# VOID01_REVA.net
KiCad netlist of a schematic drawn in EAGLE
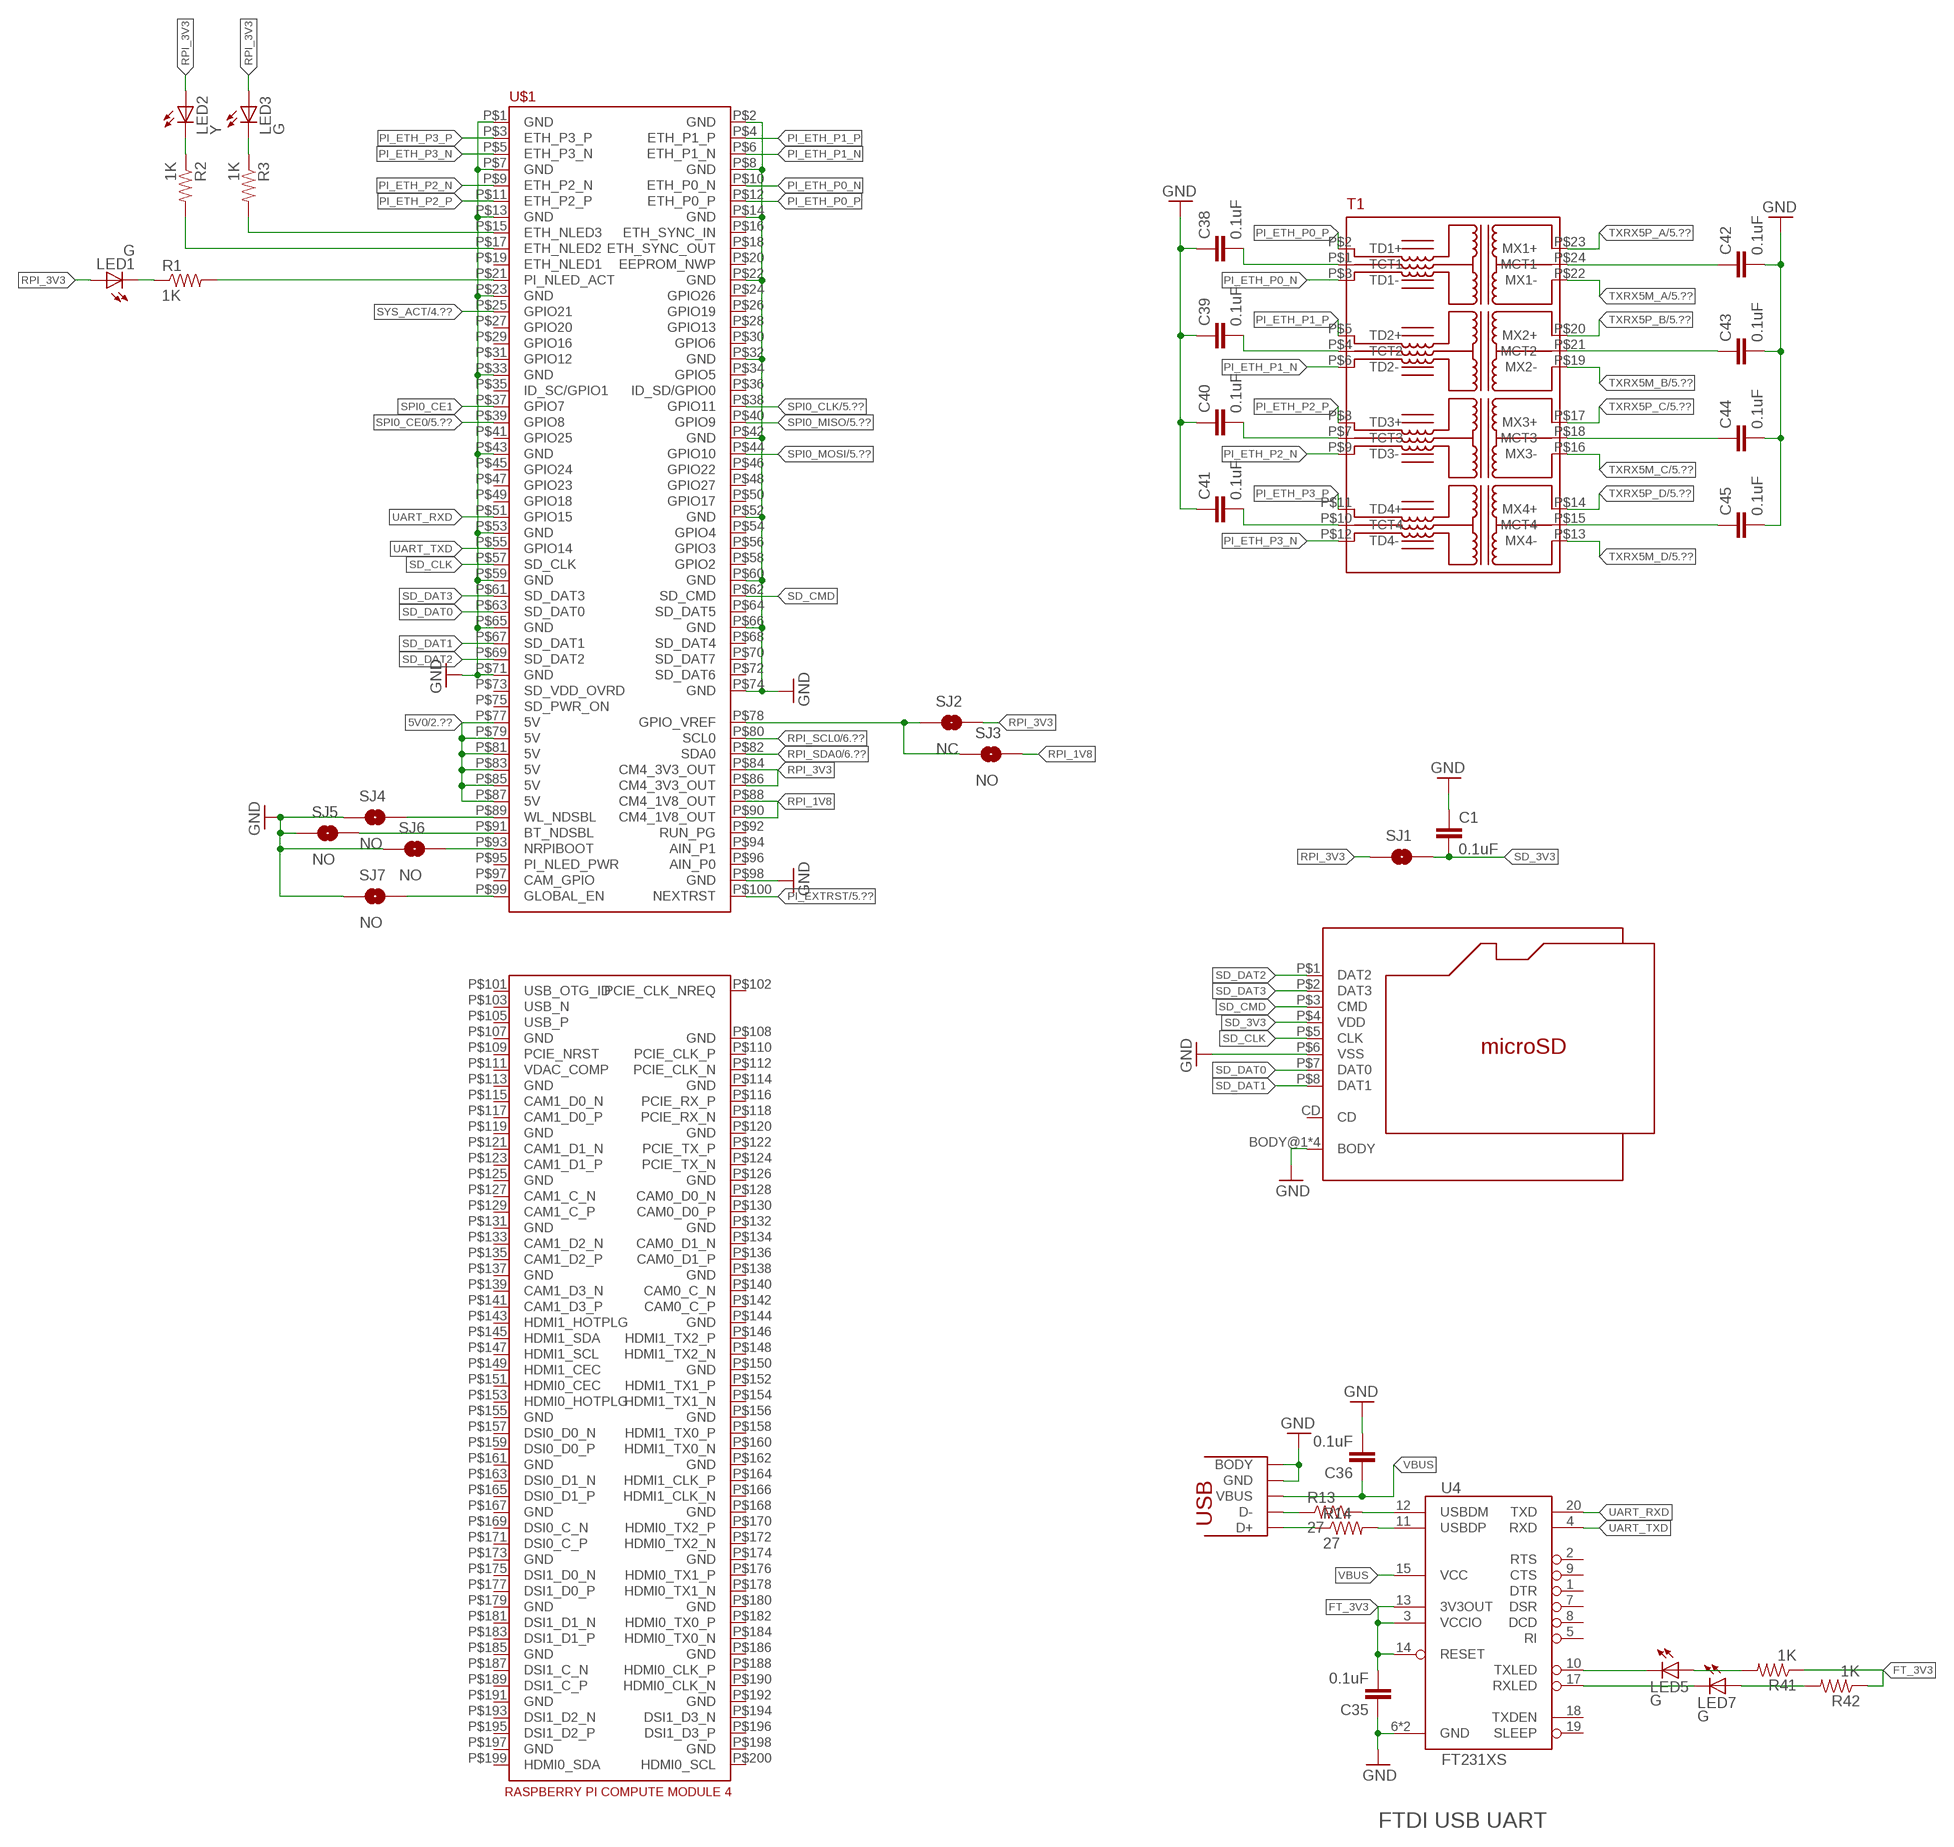
[diagram p0: schematic, sheet 1]
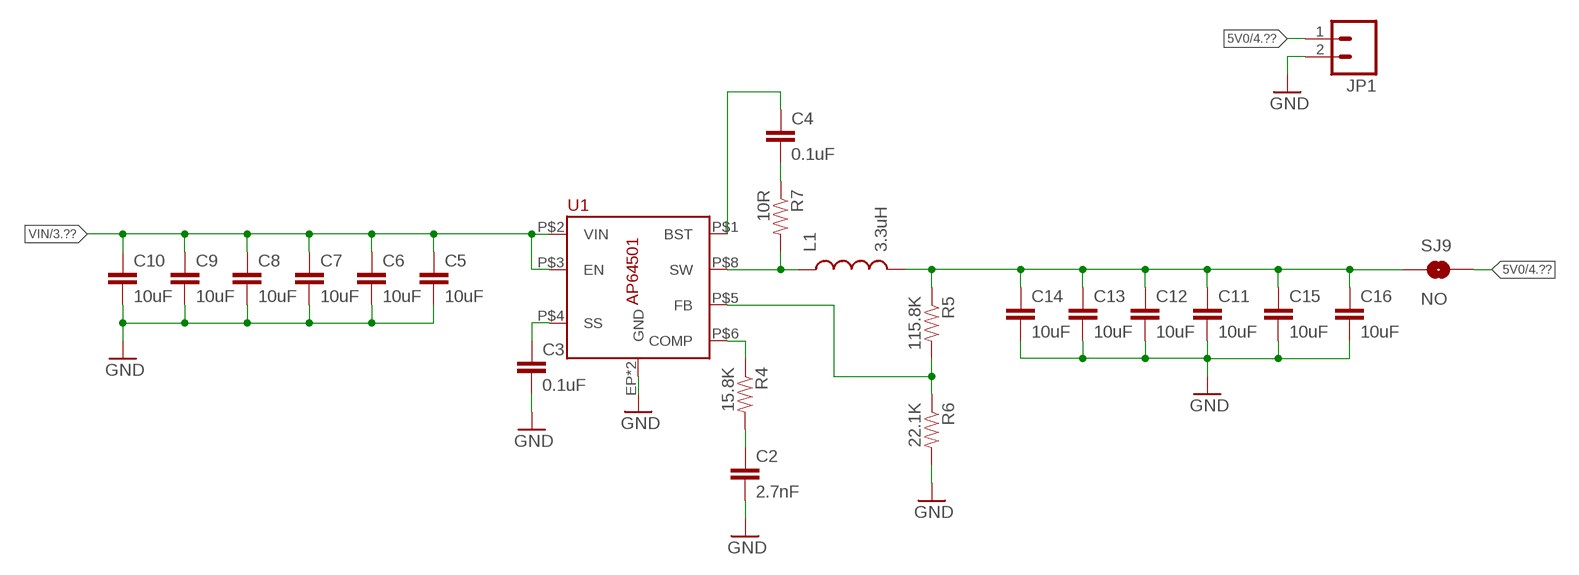
[diagram p1: schematic, sheet 2]
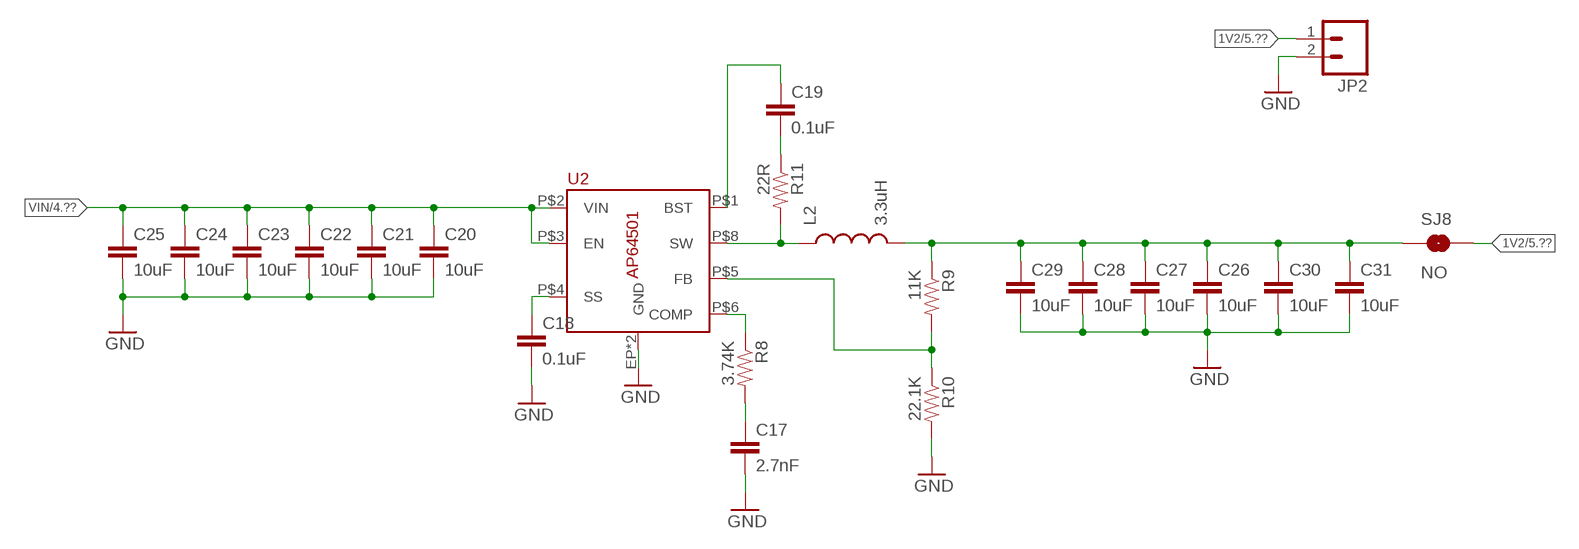
[diagram p2: schematic, sheet 3]
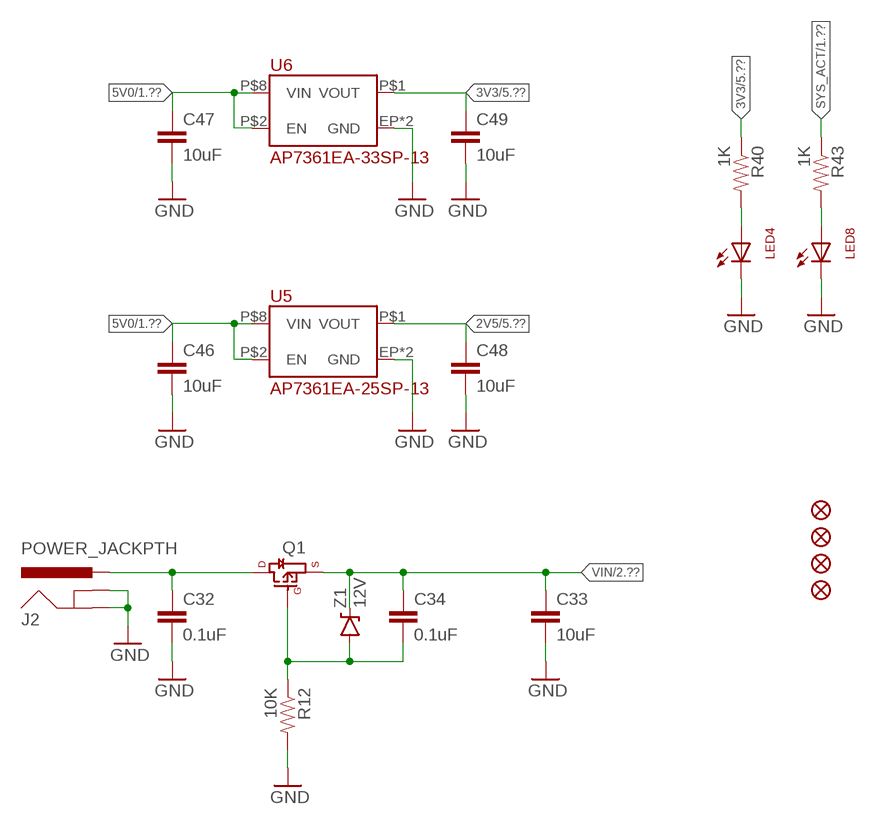
[diagram p3: schematic, sheet 4]
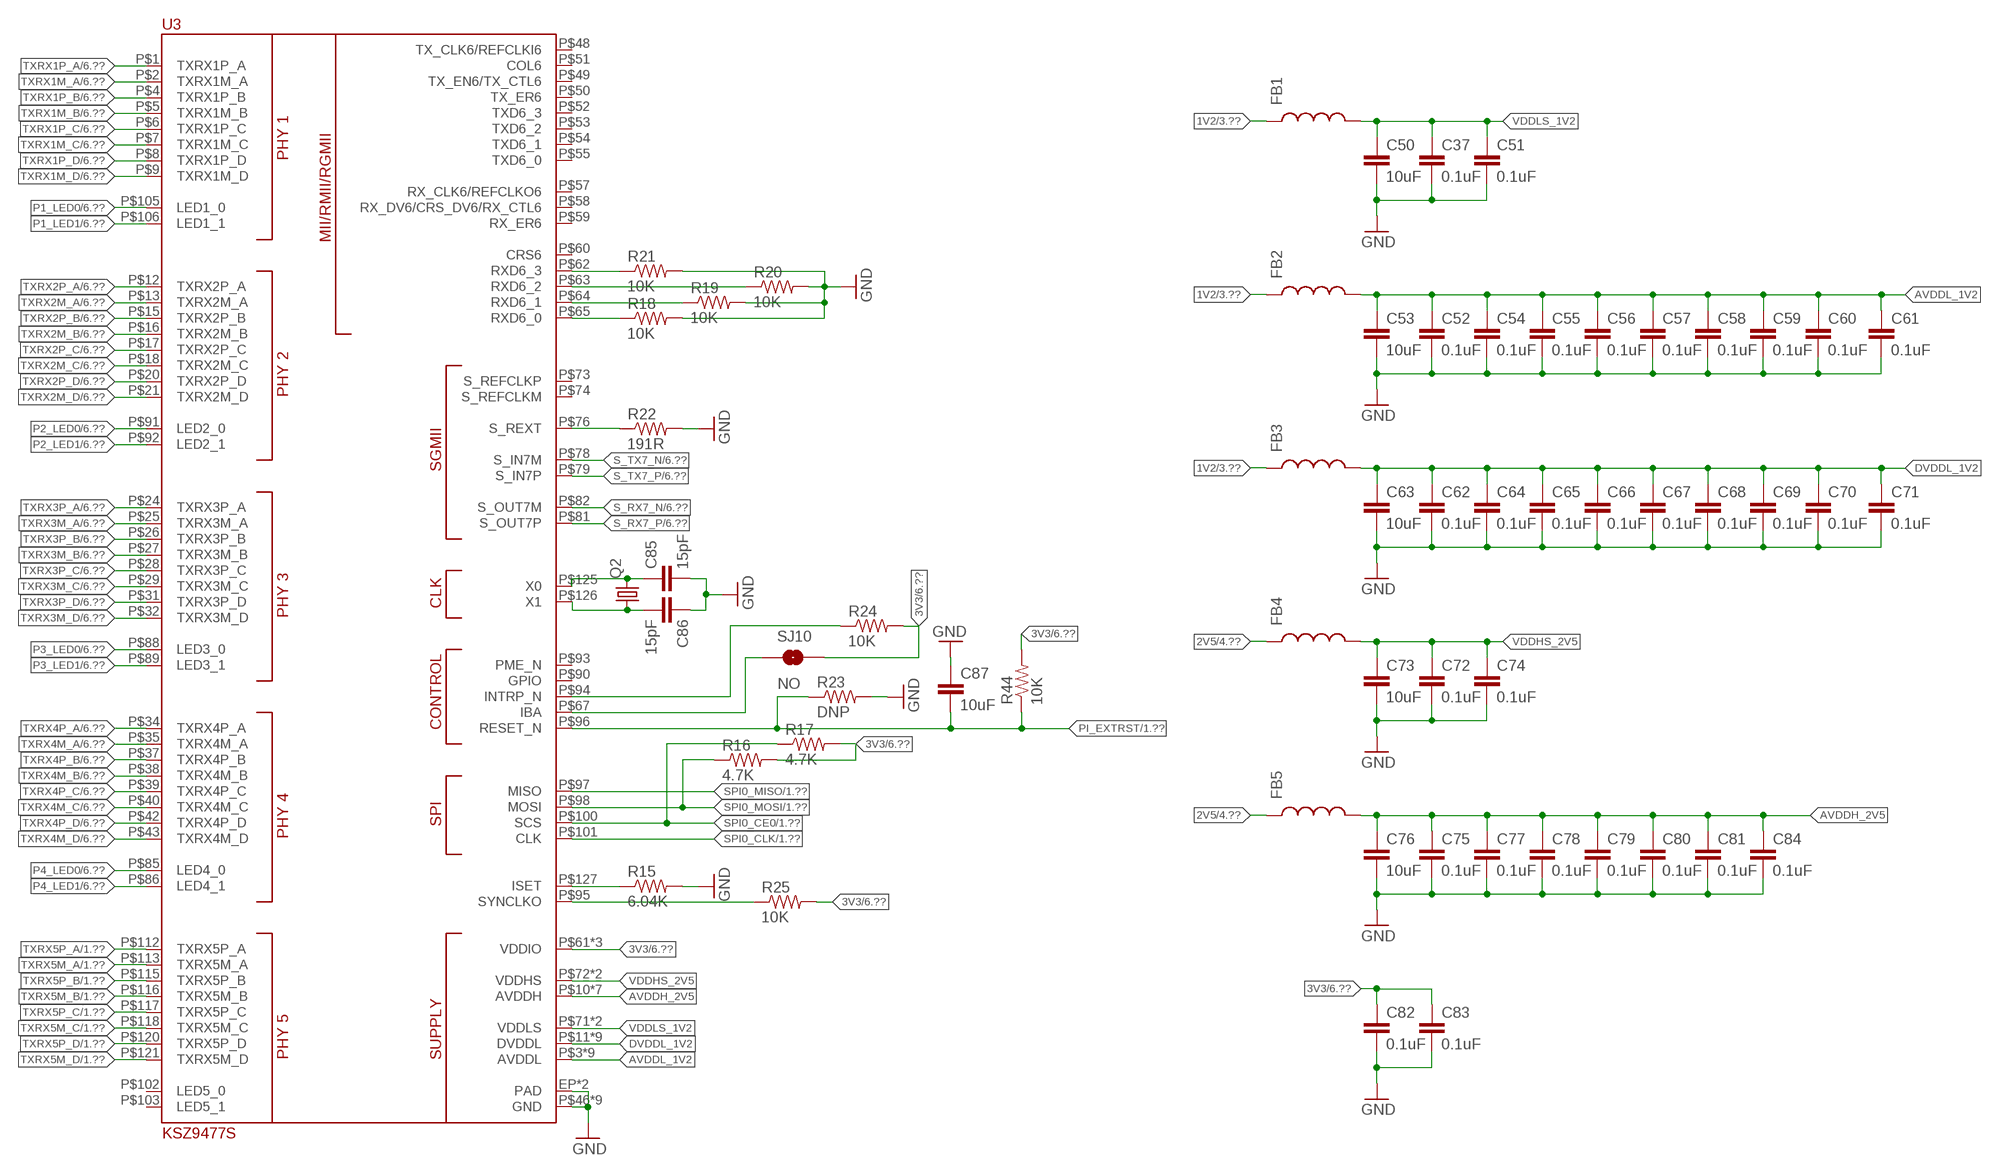
[diagram p4: schematic, sheet 5]
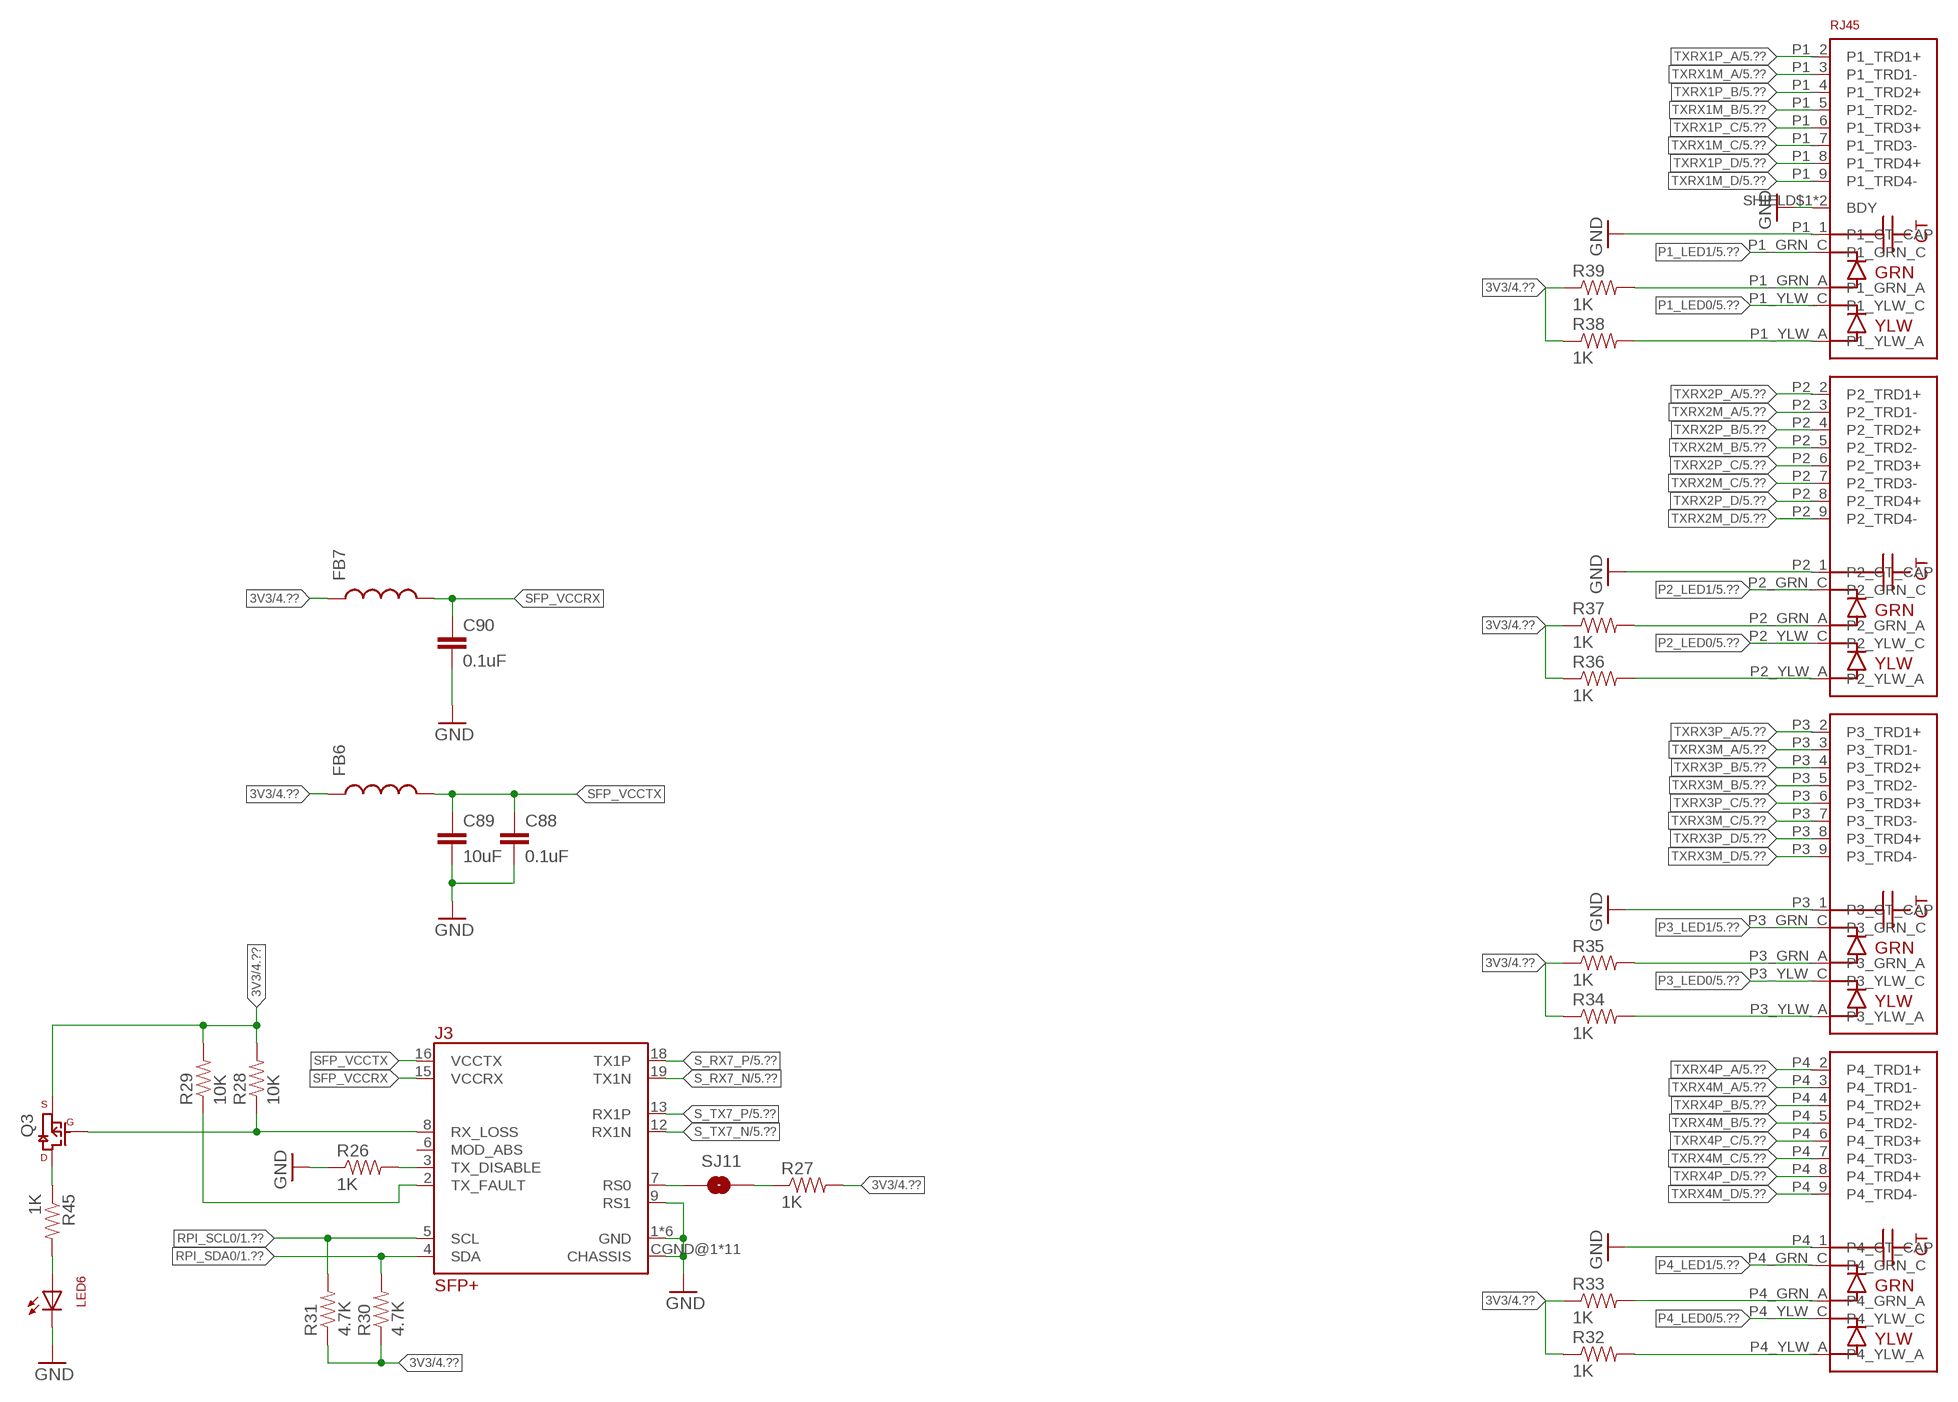
[diagram p5: schematic, sheet 6]

(export (version "E")
  (design (tool "Eeschema 10.0.6"))
  (components
    (comp (ref "C1")
      (value "0.1uF")
      (footprint "eagle-import:0603-CAP")
      (libsource (lib "eagle-import") (part "CAP0603-CAP"))
    )
    (comp (ref "C35")
      (value "0.1uF")
      (footprint "eagle-import:0603-CAP")
      (libsource (lib "eagle-import") (part "CAP0603-CAP"))
    )
    (comp (ref "C36")
      (value "0.1uF")
      (footprint "eagle-import:0603-CAP")
      (libsource (lib "eagle-import") (part "CAP0603-CAP"))
    )
    (comp (ref "C38")
      (value "0.1uF")
      (footprint "eagle-import:0603-CAP")
      (libsource (lib "eagle-import") (part "CAP0603-CAP"))
    )
    (comp (ref "C39")
      (value "0.1uF")
      (footprint "eagle-import:0603-CAP")
      (libsource (lib "eagle-import") (part "CAP0603-CAP"))
    )
    (comp (ref "C40")
      (value "0.1uF")
      (footprint "eagle-import:0603-CAP")
      (libsource (lib "eagle-import") (part "CAP0603-CAP"))
    )
    (comp (ref "C41")
      (value "0.1uF")
      (footprint "eagle-import:0603-CAP")
      (libsource (lib "eagle-import") (part "CAP0603-CAP"))
    )
    (comp (ref "C42")
      (value "0.1uF")
      (footprint "eagle-import:0603-CAP")
      (libsource (lib "eagle-import") (part "CAP0603-CAP"))
    )
    (comp (ref "C43")
      (value "0.1uF")
      (footprint "eagle-import:0603-CAP")
      (libsource (lib "eagle-import") (part "CAP0603-CAP"))
    )
    (comp (ref "C44")
      (value "0.1uF")
      (footprint "eagle-import:0603-CAP")
      (libsource (lib "eagle-import") (part "CAP0603-CAP"))
    )
    (comp (ref "C45")
      (value "0.1uF")
      (footprint "eagle-import:0603-CAP")
      (libsource (lib "eagle-import") (part "CAP0603-CAP"))
    )
    (comp (ref "J1")
      (value "MICROSD")
      (footprint "eagle-import:MSD-4-A")
      (libsource (lib "eagle-import") (part "MICROSD"))
    )
    (comp (ref "LED1")
      (value "G")
      (footprint "eagle-import:LED-0603")
      (libsource (lib "eagle-import") (part "LED0603"))
    )
    (comp (ref "LED2")
      (value "Y")
      (footprint "eagle-import:LED-0603")
      (libsource (lib "eagle-import") (part "LED0603"))
    )
    (comp (ref "LED3")
      (value "G")
      (footprint "eagle-import:LED-0603")
      (libsource (lib "eagle-import") (part "LED0603"))
    )
    (comp (ref "LED5")
      (value "G")
      (footprint "eagle-import:LED-0603")
      (libsource (lib "eagle-import") (part "LED0603"))
    )
    (comp (ref "LED7")
      (value "G")
      (footprint "eagle-import:LED-0603")
      (libsource (lib "eagle-import") (part "LED0603"))
    )
    (comp (ref "R1")
      (value "1K")
      (footprint "eagle-import:0402-RES")
      (libsource (lib "eagle-import") (part "RESISTOR0402-RES"))
    )
    (comp (ref "R2")
      (value "1K")
      (footprint "eagle-import:0402-RES")
      (libsource (lib "eagle-import") (part "RESISTOR0402-RES"))
    )
    (comp (ref "R3")
      (value "1K")
      (footprint "eagle-import:0402-RES")
      (libsource (lib "eagle-import") (part "RESISTOR0402-RES"))
    )
    (comp (ref "R13")
      (value "27")
      (footprint "eagle-import:0603-RES")
      (libsource (lib "eagle-import") (part "RESISTOR0603-RES"))
    )
    (comp (ref "R14")
      (value "27")
      (footprint "eagle-import:0603-RES")
      (libsource (lib "eagle-import") (part "RESISTOR0603-RES"))
    )
    (comp (ref "R41")
      (value "1K")
      (footprint "eagle-import:0603-RES")
      (libsource (lib "eagle-import") (part "RESISTOR0603-RES"))
    )
    (comp (ref "R42")
      (value "1K")
      (footprint "eagle-import:0603-RES")
      (libsource (lib "eagle-import") (part "RESISTOR0603-RES"))
    )
    (comp (ref "SJ1")
      (value "SOLDERJUMPERTRACE")
      (footprint "eagle-import:SJ_2S-TRACE")
      (libsource (lib "eagle-import") (part "SOLDERJUMPERTRACE"))
    )
    (comp (ref "SJ2")
      (value "NC")
      (footprint "eagle-import:SJ_2S-TRACE")
      (libsource (lib "eagle-import") (part "SOLDERJUMPERTRACE"))
    )
    (comp (ref "SJ3")
      (value "NO")
      (footprint "eagle-import:SJ_2S-NO")
      (libsource (lib "eagle-import") (part "SOLDERJUMPERNO"))
    )
    (comp (ref "SJ4")
      (value "NO")
      (footprint "eagle-import:SJ_2S-NO")
      (libsource (lib "eagle-import") (part "SOLDERJUMPERNO"))
    )
    (comp (ref "SJ5")
      (value "NO")
      (footprint "eagle-import:SJ_2S-NO")
      (libsource (lib "eagle-import") (part "SOLDERJUMPERNO"))
    )
    (comp (ref "SJ6")
      (value "NO")
      (footprint "eagle-import:SJ_2S-NO")
      (libsource (lib "eagle-import") (part "SOLDERJUMPERNO"))
    )
    (comp (ref "SJ7")
      (value "NO")
      (footprint "eagle-import:SJ_2S-NO")
      (libsource (lib "eagle-import") (part "SOLDERJUMPERNO"))
    )
    (comp (ref "T1")
      (value "HX6098NL")
      (footprint "eagle-import:HX6098NL")
      (libsource (lib "eagle-import") (part "HX6098NL"))
    )
    (comp (ref "U$1")
      (value "RPI-CM4")
      (footprint "eagle-import:RPI-CM4")
      (libsource (lib "eagle-import") (part "RPI-CM4"))
    )
    (comp (ref "U$2")
      (value "USB-MICROB")
      (footprint "eagle-import:USB-MICROB-10118192")
      (libsource (lib "eagle-import") (part "USB-MICROB"))
    )
    (comp (ref "U4")
      (value "FT231XS")
      (footprint "eagle-import:SSOP-20")
      (libsource (lib "eagle-import") (part "FT231XS"))
    )
    (comp (ref "C37")
      (value "0.1uF")
      (footprint "eagle-import:0402-CAP")
      (libsource (lib "eagle-import") (part "CAP0402-CAP"))
    )
    (comp (ref "C50")
      (value "10uF")
      (footprint "eagle-import:1206")
      (libsource (lib "eagle-import") (part "CAP1206"))
    )
    (comp (ref "C51")
      (value "0.1uF")
      (footprint "eagle-import:0402-CAP")
      (libsource (lib "eagle-import") (part "CAP0402-CAP"))
    )
    (comp (ref "C52")
      (value "0.1uF")
      (footprint "eagle-import:0402-CAP")
      (libsource (lib "eagle-import") (part "CAP0402-CAP"))
    )
    (comp (ref "C53")
      (value "10uF")
      (footprint "eagle-import:1206")
      (libsource (lib "eagle-import") (part "CAP1206"))
    )
    (comp (ref "C54")
      (value "0.1uF")
      (footprint "eagle-import:0402-CAP")
      (libsource (lib "eagle-import") (part "CAP0402-CAP"))
    )
    (comp (ref "C55")
      (value "0.1uF")
      (footprint "eagle-import:0402-CAP")
      (libsource (lib "eagle-import") (part "CAP0402-CAP"))
    )
    (comp (ref "C56")
      (value "0.1uF")
      (footprint "eagle-import:0402-CAP")
      (libsource (lib "eagle-import") (part "CAP0402-CAP"))
    )
    (comp (ref "C57")
      (value "0.1uF")
      (footprint "eagle-import:0402-CAP")
      (libsource (lib "eagle-import") (part "CAP0402-CAP"))
    )
    (comp (ref "C58")
      (value "0.1uF")
      (footprint "eagle-import:0402-CAP")
      (libsource (lib "eagle-import") (part "CAP0402-CAP"))
    )
    (comp (ref "C59")
      (value "0.1uF")
      (footprint "eagle-import:0402-CAP")
      (libsource (lib "eagle-import") (part "CAP0402-CAP"))
    )
    (comp (ref "C60")
      (value "0.1uF")
      (footprint "eagle-import:0402-CAP")
      (libsource (lib "eagle-import") (part "CAP0402-CAP"))
    )
    (comp (ref "C61")
      (value "0.1uF")
      (footprint "eagle-import:0402-CAP")
      (libsource (lib "eagle-import") (part "CAP0402-CAP"))
    )
    (comp (ref "C62")
      (value "0.1uF")
      (footprint "eagle-import:0402-CAP")
      (libsource (lib "eagle-import") (part "CAP0402-CAP"))
    )
    (comp (ref "C63")
      (value "10uF")
      (footprint "eagle-import:1206")
      (libsource (lib "eagle-import") (part "CAP1206"))
    )
    (comp (ref "C64")
      (value "0.1uF")
      (footprint "eagle-import:0402-CAP")
      (libsource (lib "eagle-import") (part "CAP0402-CAP"))
    )
    (comp (ref "C65")
      (value "0.1uF")
      (footprint "eagle-import:0402-CAP")
      (libsource (lib "eagle-import") (part "CAP0402-CAP"))
    )
    (comp (ref "C66")
      (value "0.1uF")
      (footprint "eagle-import:0402-CAP")
      (libsource (lib "eagle-import") (part "CAP0402-CAP"))
    )
    (comp (ref "C67")
      (value "0.1uF")
      (footprint "eagle-import:0402-CAP")
      (libsource (lib "eagle-import") (part "CAP0402-CAP"))
    )
    (comp (ref "C68")
      (value "0.1uF")
      (footprint "eagle-import:0402-CAP")
      (libsource (lib "eagle-import") (part "CAP0402-CAP"))
    )
    (comp (ref "C69")
      (value "0.1uF")
      (footprint "eagle-import:0402-CAP")
      (libsource (lib "eagle-import") (part "CAP0402-CAP"))
    )
    (comp (ref "C70")
      (value "0.1uF")
      (footprint "eagle-import:0402-CAP")
      (libsource (lib "eagle-import") (part "CAP0402-CAP"))
    )
    (comp (ref "C71")
      (value "0.1uF")
      (footprint "eagle-import:0402-CAP")
      (libsource (lib "eagle-import") (part "CAP0402-CAP"))
    )
    (comp (ref "C72")
      (value "0.1uF")
      (footprint "eagle-import:0402-CAP")
      (libsource (lib "eagle-import") (part "CAP0402-CAP"))
    )
    (comp (ref "C73")
      (value "10uF")
      (footprint "eagle-import:1206")
      (libsource (lib "eagle-import") (part "CAP1206"))
    )
    (comp (ref "C74")
      (value "0.1uF")
      (footprint "eagle-import:0402-CAP")
      (libsource (lib "eagle-import") (part "CAP0402-CAP"))
    )
    (comp (ref "C75")
      (value "0.1uF")
      (footprint "eagle-import:0402-CAP")
      (libsource (lib "eagle-import") (part "CAP0402-CAP"))
    )
    (comp (ref "C76")
      (value "10uF")
      (footprint "eagle-import:1206")
      (libsource (lib "eagle-import") (part "CAP1206"))
    )
    (comp (ref "C77")
      (value "0.1uF")
      (footprint "eagle-import:0402-CAP")
      (libsource (lib "eagle-import") (part "CAP0402-CAP"))
    )
    (comp (ref "C78")
      (value "0.1uF")
      (footprint "eagle-import:0402-CAP")
      (libsource (lib "eagle-import") (part "CAP0402-CAP"))
    )
    (comp (ref "C79")
      (value "0.1uF")
      (footprint "eagle-import:0402-CAP")
      (libsource (lib "eagle-import") (part "CAP0402-CAP"))
    )
    (comp (ref "C80")
      (value "0.1uF")
      (footprint "eagle-import:0402-CAP")
      (libsource (lib "eagle-import") (part "CAP0402-CAP"))
    )
    (comp (ref "C81")
      (value "0.1uF")
      (footprint "eagle-import:0402-CAP")
      (libsource (lib "eagle-import") (part "CAP0402-CAP"))
    )
    (comp (ref "C82")
      (value "0.1uF")
      (footprint "eagle-import:0402-CAP")
      (libsource (lib "eagle-import") (part "CAP0402-CAP"))
    )
    (comp (ref "C83")
      (value "0.1uF")
      (footprint "eagle-import:0402-CAP")
      (libsource (lib "eagle-import") (part "CAP0402-CAP"))
    )
    (comp (ref "C84")
      (value "0.1uF")
      (footprint "eagle-import:0402-CAP")
      (libsource (lib "eagle-import") (part "CAP0402-CAP"))
    )
    (comp (ref "C85")
      (value "15pF")
      (footprint "eagle-import:0402-CAP")
      (libsource (lib "eagle-import") (part "CAP0402-CAP"))
    )
    (comp (ref "C86")
      (value "15pF")
      (footprint "eagle-import:0402-CAP")
      (libsource (lib "eagle-import") (part "CAP0402-CAP"))
    )
    (comp (ref "C87")
      (value "10uF")
      (footprint "eagle-import:1206")
      (libsource (lib "eagle-import") (part "CAP1206"))
    )
    (comp (ref "FB1")
      (value "INDUCTOR0805")
      (footprint "eagle-import:0805")
      (libsource (lib "eagle-import") (part "INDUCTOR0805"))
    )
    (comp (ref "FB2")
      (value "INDUCTOR0805")
      (footprint "eagle-import:0805")
      (libsource (lib "eagle-import") (part "INDUCTOR0805"))
    )
    (comp (ref "FB3")
      (value "INDUCTOR0805")
      (footprint "eagle-import:0805")
      (libsource (lib "eagle-import") (part "INDUCTOR0805"))
    )
    (comp (ref "FB4")
      (value "INDUCTOR0805")
      (footprint "eagle-import:0805")
      (libsource (lib "eagle-import") (part "INDUCTOR0805"))
    )
    (comp (ref "FB5")
      (value "INDUCTOR0805")
      (footprint "eagle-import:0805")
      (libsource (lib "eagle-import") (part "INDUCTOR0805"))
    )
    (comp (ref "Q2")
      (value "CRYSTAL3.2X2.5")
      (footprint "eagle-import:CRYSTAL_3.2X2.5")
      (libsource (lib "eagle-import") (part "CRYSTAL3.2X2.5"))
    )
    (comp (ref "R15")
      (value "6.04K")
      (footprint "eagle-import:0402-RES")
      (libsource (lib "eagle-import") (part "RESISTOR0402-RES"))
    )
    (comp (ref "R16")
      (value "4.7K")
      (footprint "eagle-import:0402-RES")
      (libsource (lib "eagle-import") (part "RESISTOR0402-RES"))
    )
    (comp (ref "R17")
      (value "4.7K")
      (footprint "eagle-import:0402-RES")
      (libsource (lib "eagle-import") (part "RESISTOR0402-RES"))
    )
    (comp (ref "R18")
      (value "10K")
      (footprint "eagle-import:0402-RES")
      (libsource (lib "eagle-import") (part "RESISTOR0402-RES"))
    )
    (comp (ref "R19")
      (value "10K")
      (footprint "eagle-import:0402-RES")
      (libsource (lib "eagle-import") (part "RESISTOR0402-RES"))
    )
    (comp (ref "R20")
      (value "10K")
      (footprint "eagle-import:0402-RES")
      (libsource (lib "eagle-import") (part "RESISTOR0402-RES"))
    )
    (comp (ref "R21")
      (value "10K")
      (footprint "eagle-import:0402-RES")
      (libsource (lib "eagle-import") (part "RESISTOR0402-RES"))
    )
    (comp (ref "R22")
      (value "191R")
      (footprint "eagle-import:0402-RES")
      (libsource (lib "eagle-import") (part "RESISTOR0402-RES"))
    )
    (comp (ref "R23")
      (value "DNP")
      (footprint "eagle-import:0402-RES")
      (libsource (lib "eagle-import") (part "RESISTOR0402-RES"))
    )
    (comp (ref "R24")
      (value "10K")
      (footprint "eagle-import:0402-RES")
      (libsource (lib "eagle-import") (part "RESISTOR0402-RES"))
    )
    (comp (ref "R25")
      (value "10K")
      (footprint "eagle-import:0402-RES")
      (libsource (lib "eagle-import") (part "RESISTOR0402-RES"))
    )
    (comp (ref "R44")
      (value "10K")
      (footprint "eagle-import:0402-RES")
      (libsource (lib "eagle-import") (part "RESISTOR0402-RES"))
    )
    (comp (ref "SJ10")
      (value "NO")
      (footprint "eagle-import:SJ_2S-NO")
      (libsource (lib "eagle-import") (part "SOLDERJUMPERNO"))
    )
    (comp (ref "U3")
      (value "KSZ9477S")
      (footprint "eagle-import:TQFP-128-EP")
      (libsource (lib "eagle-import") (part "KSZ9477S"))
    )
    (comp (ref "C88")
      (value "0.1uF")
      (footprint "eagle-import:0402-CAP")
      (libsource (lib "eagle-import") (part "CAP0402-CAP"))
    )
    (comp (ref "C89")
      (value "10uF")
      (footprint "eagle-import:1206")
      (libsource (lib "eagle-import") (part "CAP1206"))
    )
    (comp (ref "C90")
      (value "0.1uF")
      (footprint "eagle-import:0402-CAP")
      (libsource (lib "eagle-import") (part "CAP0402-CAP"))
    )
    (comp (ref "FB6")
      (value "INDUCTOR0805")
      (footprint "eagle-import:0805")
      (libsource (lib "eagle-import") (part "INDUCTOR0805"))
    )
    (comp (ref "FB7")
      (value "INDUCTOR0805")
      (footprint "eagle-import:0805")
      (libsource (lib "eagle-import") (part "INDUCTOR0805"))
    )
    (comp (ref "J3")
      (value "SFP")
      (footprint "eagle-import:SFP_SOCKET_CAGE")
      (libsource (lib "eagle-import") (part "SFP+"))
    )
    (comp (ref "J4")
      (value "JXD0-4015NL")
      (footprint "eagle-import:JXD0-4015NL")
      (libsource (lib "eagle-import") (part "JXD0-4015NL"))
    )
    (comp (ref "LED6")
      (value "LED")
      (footprint "eagle-import:LED_QBL7XX80D-MP4A")
      (libsource (lib "eagle-import") (part "LED"))
    )
    (comp (ref "Q3")
      (value "MOSFET_P_CHANNELAO3423")
      (footprint "eagle-import:SOT-23")
      (libsource (lib "eagle-import") (part "MOSFET_P_CHANNELAO3423"))
    )
    (comp (ref "R26")
      (value "1K")
      (footprint "eagle-import:0402-RES")
      (libsource (lib "eagle-import") (part "RESISTOR0402-RES"))
    )
    (comp (ref "R27")
      (value "1K")
      (footprint "eagle-import:0402-RES")
      (libsource (lib "eagle-import") (part "RESISTOR0402-RES"))
    )
    (comp (ref "R28")
      (value "10K")
      (footprint "eagle-import:0603-RES")
      (libsource (lib "eagle-import") (part "RESISTOR0603-RES"))
    )
    (comp (ref "R29")
      (value "10K")
      (footprint "eagle-import:0402-RES")
      (libsource (lib "eagle-import") (part "RESISTOR0402-RES"))
    )
    (comp (ref "R30")
      (value "4.7K")
      (footprint "eagle-import:0402-RES")
      (libsource (lib "eagle-import") (part "RESISTOR0402-RES"))
    )
    (comp (ref "R31")
      (value "4.7K")
      (footprint "eagle-import:0402-RES")
      (libsource (lib "eagle-import") (part "RESISTOR0402-RES"))
    )
    (comp (ref "R32")
      (value "1K")
      (footprint "eagle-import:0603-RES")
      (libsource (lib "eagle-import") (part "RESISTOR0603-RES"))
    )
    (comp (ref "R33")
      (value "1K")
      (footprint "eagle-import:0603-RES")
      (libsource (lib "eagle-import") (part "RESISTOR0603-RES"))
    )
    (comp (ref "R34")
      (value "1K")
      (footprint "eagle-import:0603-RES")
      (libsource (lib "eagle-import") (part "RESISTOR0603-RES"))
    )
    (comp (ref "R35")
      (value "1K")
      (footprint "eagle-import:0603-RES")
      (libsource (lib "eagle-import") (part "RESISTOR0603-RES"))
    )
    (comp (ref "R36")
      (value "1K")
      (footprint "eagle-import:0603-RES")
      (libsource (lib "eagle-import") (part "RESISTOR0603-RES"))
    )
    (comp (ref "R37")
      (value "1K")
      (footprint "eagle-import:0603-RES")
      (libsource (lib "eagle-import") (part "RESISTOR0603-RES"))
    )
    (comp (ref "R38")
      (value "1K")
      (footprint "eagle-import:0603-RES")
      (libsource (lib "eagle-import") (part "RESISTOR0603-RES"))
    )
    (comp (ref "R39")
      (value "1K")
      (footprint "eagle-import:0603-RES")
      (libsource (lib "eagle-import") (part "RESISTOR0603-RES"))
    )
    (comp (ref "R45")
      (value "1K")
      (footprint "eagle-import:0603-RES")
      (libsource (lib "eagle-import") (part "RESISTOR0603-RES"))
    )
    (comp (ref "SJ11")
      (value "SOLDERJUMPERNO")
      (footprint "eagle-import:SJ_2S-NO")
      (libsource (lib "eagle-import") (part "SOLDERJUMPERNO"))
    )
    (comp (ref "C17")
      (value "2.7nF")
      (footprint "eagle-import:0603-CAP")
      (libsource (lib "eagle-import") (part "CAP0603-CAP"))
    )
    (comp (ref "C18")
      (value "0.1uF")
      (footprint "eagle-import:0603-CAP")
      (libsource (lib "eagle-import") (part "CAP0603-CAP"))
    )
    (comp (ref "C19")
      (value "0.1uF")
      (footprint "eagle-import:0603-CAP")
      (libsource (lib "eagle-import") (part "CAP0603-CAP"))
    )
    (comp (ref "C20")
      (value "10uF")
      (footprint "eagle-import:1206")
      (libsource (lib "eagle-import") (part "CAP1206"))
    )
    (comp (ref "C21")
      (value "10uF")
      (footprint "eagle-import:1206")
      (libsource (lib "eagle-import") (part "CAP1206"))
    )
    (comp (ref "C22")
      (value "10uF")
      (footprint "eagle-import:1206")
      (libsource (lib "eagle-import") (part "CAP1206"))
    )
    (comp (ref "C23")
      (value "10uF")
      (footprint "eagle-import:1206")
      (libsource (lib "eagle-import") (part "CAP1206"))
    )
    (comp (ref "C24")
      (value "10uF")
      (footprint "eagle-import:1206")
      (libsource (lib "eagle-import") (part "CAP1206"))
    )
    (comp (ref "C25")
      (value "10uF")
      (footprint "eagle-import:1206")
      (libsource (lib "eagle-import") (part "CAP1206"))
    )
    (comp (ref "C26")
      (value "10uF")
      (footprint "eagle-import:1206")
      (libsource (lib "eagle-import") (part "CAP1206"))
    )
    (comp (ref "C27")
      (value "10uF")
      (footprint "eagle-import:1206")
      (libsource (lib "eagle-import") (part "CAP1206"))
    )
    (comp (ref "C28")
      (value "10uF")
      (footprint "eagle-import:1206")
      (libsource (lib "eagle-import") (part "CAP1206"))
    )
    (comp (ref "C29")
      (value "10uF")
      (footprint "eagle-import:1206")
      (libsource (lib "eagle-import") (part "CAP1206"))
    )
    (comp (ref "C30")
      (value "10uF")
      (footprint "eagle-import:1206")
      (libsource (lib "eagle-import") (part "CAP1206"))
    )
    (comp (ref "C31")
      (value "10uF")
      (footprint "eagle-import:1206")
      (libsource (lib "eagle-import") (part "CAP1206"))
    )
    (comp (ref "JP2")
      (value "M02PTH3")
      (footprint "eagle-import:1X02_LONGPADS")
      (libsource (lib "eagle-import") (part "M02PTH3"))
    )
    (comp (ref "L2")
      (value "3.3uH")
      (footprint "eagle-import:SRN6045TA")
      (libsource (lib "eagle-import") (part "INDUCTORSRN6045TA"))
    )
    (comp (ref "R8")
      (value "3.74K")
      (footprint "eagle-import:0603-RES")
      (libsource (lib "eagle-import") (part "RESISTOR0603-RES"))
    )
    (comp (ref "R9")
      (value "11K")
      (footprint "eagle-import:0603-RES")
      (libsource (lib "eagle-import") (part "RESISTOR0603-RES"))
    )
    (comp (ref "R10")
      (value "22.1K")
      (footprint "eagle-import:0603-RES")
      (libsource (lib "eagle-import") (part "RESISTOR0603-RES"))
    )
    (comp (ref "R11")
      (value "22R")
      (footprint "eagle-import:0603-RES")
      (libsource (lib "eagle-import") (part "RESISTOR0603-RES"))
    )
    (comp (ref "SJ8")
      (value "NO")
      (footprint "eagle-import:SJ_2S-NO")
      (libsource (lib "eagle-import") (part "SOLDERJUMPERNO"))
    )
    (comp (ref "U2")
      (value "AP64501")
      (footprint "eagle-import:SO-8EP")
      (libsource (lib "eagle-import") (part "AP64501"))
    )
    (comp (ref "C2")
      (value "2.7nF")
      (footprint "eagle-import:0603-CAP")
      (libsource (lib "eagle-import") (part "CAP0603-CAP"))
    )
    (comp (ref "C3")
      (value "0.1uF")
      (footprint "eagle-import:0603-CAP")
      (libsource (lib "eagle-import") (part "CAP0603-CAP"))
    )
    (comp (ref "C4")
      (value "0.1uF")
      (footprint "eagle-import:0603-CAP")
      (libsource (lib "eagle-import") (part "CAP0603-CAP"))
    )
    (comp (ref "C5")
      (value "10uF")
      (footprint "eagle-import:1206")
      (libsource (lib "eagle-import") (part "CAP1206"))
    )
    (comp (ref "C6")
      (value "10uF")
      (footprint "eagle-import:1206")
      (libsource (lib "eagle-import") (part "CAP1206"))
    )
    (comp (ref "C7")
      (value "10uF")
      (footprint "eagle-import:1206")
      (libsource (lib "eagle-import") (part "CAP1206"))
    )
    (comp (ref "C8")
      (value "10uF")
      (footprint "eagle-import:1206")
      (libsource (lib "eagle-import") (part "CAP1206"))
    )
    (comp (ref "C9")
      (value "10uF")
      (footprint "eagle-import:1206")
      (libsource (lib "eagle-import") (part "CAP1206"))
    )
    (comp (ref "C10")
      (value "10uF")
      (footprint "eagle-import:1206")
      (libsource (lib "eagle-import") (part "CAP1206"))
    )
    (comp (ref "C11")
      (value "10uF")
      (footprint "eagle-import:1206")
      (libsource (lib "eagle-import") (part "CAP1206"))
    )
    (comp (ref "C12")
      (value "10uF")
      (footprint "eagle-import:1206")
      (libsource (lib "eagle-import") (part "CAP1206"))
    )
    (comp (ref "C13")
      (value "10uF")
      (footprint "eagle-import:1206")
      (libsource (lib "eagle-import") (part "CAP1206"))
    )
    (comp (ref "C14")
      (value "10uF")
      (footprint "eagle-import:1206")
      (libsource (lib "eagle-import") (part "CAP1206"))
    )
    (comp (ref "C15")
      (value "10uF")
      (footprint "eagle-import:1206")
      (libsource (lib "eagle-import") (part "CAP1206"))
    )
    (comp (ref "C16")
      (value "10uF")
      (footprint "eagle-import:1206")
      (libsource (lib "eagle-import") (part "CAP1206"))
    )
    (comp (ref "JP1")
      (value "M02PTH3")
      (footprint "eagle-import:1X02_LONGPADS")
      (libsource (lib "eagle-import") (part "M02PTH3"))
    )
    (comp (ref "L1")
      (value "3.3uH")
      (footprint "eagle-import:SRN6045TA")
      (libsource (lib "eagle-import") (part "INDUCTORSRN6045TA"))
    )
    (comp (ref "R4")
      (value "15.8K")
      (footprint "eagle-import:0603-RES")
      (libsource (lib "eagle-import") (part "RESISTOR0603-RES"))
    )
    (comp (ref "R5")
      (value "115.8K")
      (footprint "eagle-import:0603-RES")
      (libsource (lib "eagle-import") (part "RESISTOR0603-RES"))
    )
    (comp (ref "R6")
      (value "22.1K")
      (footprint "eagle-import:0603-RES")
      (libsource (lib "eagle-import") (part "RESISTOR0603-RES"))
    )
    (comp (ref "R7")
      (value "10R")
      (footprint "eagle-import:0603-RES")
      (libsource (lib "eagle-import") (part "RESISTOR0603-RES"))
    )
    (comp (ref "SJ9")
      (value "NO")
      (footprint "eagle-import:SJ_2S-NO")
      (libsource (lib "eagle-import") (part "SOLDERJUMPERNO"))
    )
    (comp (ref "U1")
      (value "AP64501")
      (footprint "eagle-import:SO-8EP")
      (libsource (lib "eagle-import") (part "AP64501"))
    )
    (comp (ref "C32")
      (value "0.1uF")
      (footprint "eagle-import:0603-CAP")
      (libsource (lib "eagle-import") (part "CAP0603-CAP"))
    )
    (comp (ref "C33")
      (value "10uF")
      (footprint "eagle-import:1206")
      (libsource (lib "eagle-import") (part "CAP1206"))
    )
    (comp (ref "C34")
      (value "0.1uF")
      (footprint "eagle-import:0603-CAP")
      (libsource (lib "eagle-import") (part "CAP0603-CAP"))
    )
    (comp (ref "C46")
      (value "10uF")
      (footprint "eagle-import:1206")
      (libsource (lib "eagle-import") (part "CAP1206"))
    )
    (comp (ref "C47")
      (value "10uF")
      (footprint "eagle-import:1206")
      (libsource (lib "eagle-import") (part "CAP1206"))
    )
    (comp (ref "C48")
      (value "10uF")
      (footprint "eagle-import:1206")
      (libsource (lib "eagle-import") (part "CAP1206"))
    )
    (comp (ref "C49")
      (value "10uF")
      (footprint "eagle-import:1206")
      (libsource (lib "eagle-import") (part "CAP1206"))
    )
    (comp (ref "FID1")
      (value "FIDUCIAL")
      (footprint "eagle-import:FIDUCIAL")
      (libsource (lib "eagle-import") (part "FIDUCIAL"))
    )
    (comp (ref "FID2")
      (value "FIDUCIAL")
      (footprint "eagle-import:FIDUCIAL")
      (libsource (lib "eagle-import") (part "FIDUCIAL"))
    )
    (comp (ref "FID3")
      (value "FIDUCIAL")
      (footprint "eagle-import:FIDUCIAL")
      (libsource (lib "eagle-import") (part "FIDUCIAL"))
    )
    (comp (ref "FID4")
      (value "FIDUCIAL")
      (footprint "eagle-import:FIDUCIAL")
      (libsource (lib "eagle-import") (part "FIDUCIAL"))
    )
    (comp (ref "J2")
      (value "POWER_JACKPTH")
      (footprint "eagle-import:POWER_JACK_PTH")
      (libsource (lib "eagle-import") (part "POWER_JACKPTH"))
    )
    (comp (ref "LED4")
      (value "LED")
      (footprint "eagle-import:LED_QBL7XX80D-MP4A")
      (libsource (lib "eagle-import") (part "LED"))
    )
    (comp (ref "LED8")
      (value "LED")
      (footprint "eagle-import:LED_QBL7XX80D-MP4A")
      (libsource (lib "eagle-import") (part "LED"))
    )
    (comp (ref "Q1")
      (value "MOSFET_P_CHANNELDMP4015SSS")
      (footprint "eagle-import:SO08")
      (libsource (lib "eagle-import") (part "MOSFET_P_CHANNELDMP4015SSS"))
    )
    (comp (ref "R12")
      (value "10K")
      (footprint "eagle-import:0603-RES")
      (libsource (lib "eagle-import") (part "RESISTOR0603-RES"))
    )
    (comp (ref "R40")
      (value "1K")
      (footprint "eagle-import:0603-RES")
      (libsource (lib "eagle-import") (part "RESISTOR0603-RES"))
    )
    (comp (ref "R43")
      (value "1K")
      (footprint "eagle-import:0603-RES")
      (libsource (lib "eagle-import") (part "RESISTOR0603-RES"))
    )
    (comp (ref "U5")
      (value "AP7361EA-25SP-13")
      (footprint "eagle-import:SO-8EP")
      (libsource (lib "eagle-import") (part "AP7361EA_SO8_EP"))
    )
    (comp (ref "U6")
      (value "AP7361EA-33SP-13")
      (footprint "eagle-import:SO-8EP")
      (libsource (lib "eagle-import") (part "AP7361EA_SO8_EP"))
    )
    (comp (ref "Z1")
      (value "12V")
      (footprint "eagle-import:SOT-23")
      (libsource (lib "eagle-import") (part "DIODE-ZENERSOT-23"))
    )
  )
  (nets
    (net (code "1") (name "1V2") (class "Default")
      (node (ref "FB1") (pin "1") (pinfunction "1_1") (pintype "passive"))
      (node (ref "FB2") (pin "1") (pinfunction "1_1") (pintype "passive"))
      (node (ref "FB3") (pin "1") (pinfunction "1_1") (pintype "passive"))
      (node (ref "JP2") (pin "1") (pinfunction "1_1") (pintype "passive"))
      (node (ref "SJ8") (pin "2") (pinfunction "2_2") (pintype "passive"))
    )
    (net (code "2") (name "2V5") (class "Default")
      (node (ref "C48") (pin "1") (pinfunction "1_1") (pintype "passive"))
      (node (ref "FB4") (pin "1") (pinfunction "1_1") (pintype "passive"))
      (node (ref "FB5") (pin "1") (pinfunction "1_1") (pintype "passive"))
      (node (ref "U5") (pin "P$1") (pinfunction "VOUT_P$1") (pintype "bidirectional"))
    )
    (net (code "3") (name "3V3") (class "Default")
      (node (ref "C49") (pin "1") (pinfunction "1_1") (pintype "passive"))
      (node (ref "C82") (pin "1") (pinfunction "1_1") (pintype "passive"))
      (node (ref "C83") (pin "1") (pinfunction "1_1") (pintype "passive"))
      (node (ref "FB6") (pin "1") (pinfunction "1_1") (pintype "passive"))
      (node (ref "FB7") (pin "1") (pinfunction "1_1") (pintype "passive"))
      (node (ref "Q3") (pin "2") (pinfunction "S_2") (pintype "bidirectional"))
      (node (ref "R16") (pin "2") (pinfunction "2_2") (pintype "passive"))
      (node (ref "R17") (pin "2") (pinfunction "2_2") (pintype "passive"))
      (node (ref "R24") (pin "2") (pinfunction "2_2") (pintype "passive"))
      (node (ref "R25") (pin "2") (pinfunction "2_2") (pintype "passive"))
      (node (ref "R27") (pin "2") (pinfunction "2_2") (pintype "passive"))
      (node (ref "R28") (pin "2") (pinfunction "2_2") (pintype "passive"))
      (node (ref "R29") (pin "2") (pinfunction "2_2") (pintype "passive"))
      (node (ref "R30") (pin "1") (pinfunction "1_1") (pintype "passive"))
      (node (ref "R31") (pin "1") (pinfunction "1_1") (pintype "passive"))
      (node (ref "R32") (pin "1") (pinfunction "1_1") (pintype "passive"))
      (node (ref "R33") (pin "1") (pinfunction "1_1") (pintype "passive"))
      (node (ref "R34") (pin "1") (pinfunction "1_1") (pintype "passive"))
      (node (ref "R35") (pin "1") (pinfunction "1_1") (pintype "passive"))
      (node (ref "R36") (pin "1") (pinfunction "1_1") (pintype "passive"))
      (node (ref "R37") (pin "1") (pinfunction "1_1") (pintype "passive"))
      (node (ref "R38") (pin "1") (pinfunction "1_1") (pintype "passive"))
      (node (ref "R39") (pin "1") (pinfunction "1_1") (pintype "passive"))
      (node (ref "R40") (pin "1") (pinfunction "1_1") (pintype "passive"))
      (node (ref "R44") (pin "2") (pinfunction "2_2") (pintype "passive"))
      (node (ref "SJ10") (pin "2") (pinfunction "2_2") (pintype "passive"))
      (node (ref "U3") (pin "P$61") (pinfunction "VDDIO_P$61") (pintype "bidirectional"))
      (node (ref "U3") (pin "P$68") (pinfunction "VDDIO_P$68") (pintype "bidirectional"))
      (node (ref "U3") (pin "P$99") (pinfunction "VDDIO_P$99") (pintype "bidirectional"))
      (node (ref "U6") (pin "P$1") (pinfunction "VOUT_P$1") (pintype "bidirectional"))
    )
    (net (code "4") (name "5V0") (class "Default")
      (node (ref "C46") (pin "1") (pinfunction "1_1") (pintype "passive"))
      (node (ref "C47") (pin "1") (pinfunction "1_1") (pintype "passive"))
      (node (ref "JP1") (pin "1") (pinfunction "1_1") (pintype "passive"))
      (node (ref "SJ9") (pin "2") (pinfunction "2_2") (pintype "passive"))
      (node (ref "U$1") (pin "P$77") (pinfunction "5V_P$77") (pintype "bidirectional"))
      (node (ref "U$1") (pin "P$79") (pinfunction "5V_P$79") (pintype "bidirectional"))
      (node (ref "U$1") (pin "P$81") (pinfunction "5V_P$81") (pintype "bidirectional"))
      (node (ref "U$1") (pin "P$83") (pinfunction "5V_P$83") (pintype "bidirectional"))
      (node (ref "U$1") (pin "P$85") (pinfunction "5V_P$85") (pintype "bidirectional"))
      (node (ref "U$1") (pin "P$87") (pinfunction "5V_P$87") (pintype "bidirectional"))
      (node (ref "U5") (pin "P$2") (pinfunction "EN_P$2") (pintype "bidirectional"))
      (node (ref "U5") (pin "P$8") (pinfunction "VIN_P$8") (pintype "bidirectional"))
      (node (ref "U6") (pin "P$2") (pinfunction "EN_P$2") (pintype "bidirectional"))
      (node (ref "U6") (pin "P$8") (pinfunction "VIN_P$8") (pintype "bidirectional"))
    )
    (net (code "5") (name "AVDDH_2V5") (class "Default")
      (node (ref "C75") (pin "1") (pinfunction "1_1") (pintype "passive"))
      (node (ref "C76") (pin "1") (pinfunction "1_1") (pintype "passive"))
      (node (ref "C77") (pin "1") (pinfunction "1_1") (pintype "passive"))
      (node (ref "C78") (pin "1") (pinfunction "1_1") (pintype "passive"))
      (node (ref "C79") (pin "1") (pinfunction "1_1") (pintype "passive"))
      (node (ref "C80") (pin "1") (pinfunction "1_1") (pintype "passive"))
      (node (ref "C81") (pin "1") (pinfunction "1_1") (pintype "passive"))
      (node (ref "C84") (pin "1") (pinfunction "1_1") (pintype "passive"))
      (node (ref "FB5") (pin "2") (pinfunction "2_2") (pintype "passive"))
      (node (ref "U3") (pin "P$10") (pinfunction "AVDDH_P$10") (pintype "bidirectional"))
      (node (ref "U3") (pin "P$111") (pinfunction "AVDDH_P$111") (pintype "bidirectional"))
      (node (ref "U3") (pin "P$122") (pinfunction "AVDDH_P$122") (pintype "bidirectional"))
      (node (ref "U3") (pin "P$128") (pinfunction "AVDDH_P$128") (pintype "bidirectional"))
      (node (ref "U3") (pin "P$22") (pinfunction "AVDDH_P$22") (pintype "bidirectional"))
      (node (ref "U3") (pin "P$33") (pinfunction "AVDDH_P$33") (pintype "bidirectional"))
      (node (ref "U3") (pin "P$44") (pinfunction "AVDDH_P$44") (pintype "bidirectional"))
    )
    (net (code "6") (name "AVDDL_1V2") (class "Default")
      (node (ref "C52") (pin "1") (pinfunction "1_1") (pintype "passive"))
      (node (ref "C53") (pin "1") (pinfunction "1_1") (pintype "passive"))
      (node (ref "C54") (pin "1") (pinfunction "1_1") (pintype "passive"))
      (node (ref "C55") (pin "1") (pinfunction "1_1") (pintype "passive"))
      (node (ref "C56") (pin "1") (pinfunction "1_1") (pintype "passive"))
      (node (ref "C57") (pin "1") (pinfunction "1_1") (pintype "passive"))
      (node (ref "C58") (pin "1") (pinfunction "1_1") (pintype "passive"))
      (node (ref "C59") (pin "1") (pinfunction "1_1") (pintype "passive"))
      (node (ref "C60") (pin "1") (pinfunction "1_1") (pintype "passive"))
      (node (ref "C61") (pin "1") (pinfunction "1_1") (pintype "passive"))
      (node (ref "FB2") (pin "2") (pinfunction "2_2") (pintype "passive"))
      (node (ref "U3") (pin "P$114") (pinfunction "AVDDL_P$114") (pintype "bidirectional"))
      (node (ref "U3") (pin "P$119") (pinfunction "AVDDL_P$119") (pintype "bidirectional"))
      (node (ref "U3") (pin "P$124") (pinfunction "AVDDL_P$124") (pintype "bidirectional"))
      (node (ref "U3") (pin "P$14") (pinfunction "AVDDL_P$14") (pintype "bidirectional"))
      (node (ref "U3") (pin "P$19") (pinfunction "AVDDL_P$19") (pintype "bidirectional"))
      (node (ref "U3") (pin "P$3") (pinfunction "AVDDL_P$3") (pintype "bidirectional"))
      (node (ref "U3") (pin "P$30") (pinfunction "AVDDL_P$30") (pintype "bidirectional"))
      (node (ref "U3") (pin "P$36") (pinfunction "AVDDL_P$36") (pintype "bidirectional"))
      (node (ref "U3") (pin "P$41") (pinfunction "AVDDL_P$41") (pintype "bidirectional"))
    )
    (net (code "7") (name "DVDDL_1V2") (class "Default")
      (node (ref "C62") (pin "1") (pinfunction "1_1") (pintype "passive"))
      (node (ref "C63") (pin "1") (pinfunction "1_1") (pintype "passive"))
      (node (ref "C64") (pin "1") (pinfunction "1_1") (pintype "passive"))
      (node (ref "C65") (pin "1") (pinfunction "1_1") (pintype "passive"))
      (node (ref "C66") (pin "1") (pinfunction "1_1") (pintype "passive"))
      (node (ref "C67") (pin "1") (pinfunction "1_1") (pintype "passive"))
      (node (ref "C68") (pin "1") (pinfunction "1_1") (pintype "passive"))
      (node (ref "C69") (pin "1") (pinfunction "1_1") (pintype "passive"))
      (node (ref "C70") (pin "1") (pinfunction "1_1") (pintype "passive"))
      (node (ref "C71") (pin "1") (pinfunction "1_1") (pintype "passive"))
      (node (ref "FB3") (pin "2") (pinfunction "2_2") (pintype "passive"))
      (node (ref "U3") (pin "P$104") (pinfunction "DVDDL_P$104") (pintype "bidirectional"))
      (node (ref "U3") (pin "P$11") (pinfunction "DVDDL_P$11") (pintype "bidirectional"))
      (node (ref "U3") (pin "P$110") (pinfunction "DVDDL_P$110") (pintype "bidirectional"))
      (node (ref "U3") (pin "P$23") (pinfunction "DVDDL_P$23") (pintype "bidirectional"))
      (node (ref "U3") (pin "P$45") (pinfunction "DVDDL_P$45") (pintype "bidirectional"))
      (node (ref "U3") (pin "P$56") (pinfunction "DVDDL_P$56") (pintype "bidirectional"))
      (node (ref "U3") (pin "P$66") (pinfunction "DVDDL_P$66") (pintype "bidirectional"))
      (node (ref "U3") (pin "P$70") (pinfunction "DVDDL_P$70") (pintype "bidirectional"))
      (node (ref "U3") (pin "P$87") (pinfunction "DVDDL_P$87") (pintype "bidirectional"))
    )
    (net (code "8") (name "FT_3V3") (class "Default")
      (node (ref "C35") (pin "2") (pinfunction "2_2") (pintype "passive"))
      (node (ref "R41") (pin "1") (pinfunction "1_1") (pintype "passive"))
      (node (ref "R42") (pin "1") (pinfunction "1_1") (pintype "passive"))
      (node (ref "U4") (pin "13") (pinfunction "3V3OUT_13") (pintype "output"))
      (node (ref "U4") (pin "14") (pinfunction "RESET_14") (pintype "input"))
      (node (ref "U4") (pin "3") (pinfunction "VCCIO_3") (pintype "power_in"))
    )
    (net (code "9") (name "GND") (class "Default")
      (node (ref "C1") (pin "1") (pinfunction "1_1") (pintype "passive"))
      (node (ref "C10") (pin "2") (pinfunction "2_2") (pintype "passive"))
      (node (ref "C11") (pin "2") (pinfunction "2_2") (pintype "passive"))
      (node (ref "C12") (pin "2") (pinfunction "2_2") (pintype "passive"))
      (node (ref "C13") (pin "2") (pinfunction "2_2") (pintype "passive"))
      (node (ref "C14") (pin "2") (pinfunction "2_2") (pintype "passive"))
      (node (ref "C15") (pin "2") (pinfunction "2_2") (pintype "passive"))
      (node (ref "C16") (pin "2") (pinfunction "2_2") (pintype "passive"))
      (node (ref "C17") (pin "2") (pinfunction "2_2") (pintype "passive"))
      (node (ref "C18") (pin "2") (pinfunction "2_2") (pintype "passive"))
      (node (ref "C2") (pin "2") (pinfunction "2_2") (pintype "passive"))
      (node (ref "C20") (pin "2") (pinfunction "2_2") (pintype "passive"))
      (node (ref "C21") (pin "2") (pinfunction "2_2") (pintype "passive"))
      (node (ref "C22") (pin "2") (pinfunction "2_2") (pintype "passive"))
      (node (ref "C23") (pin "2") (pinfunction "2_2") (pintype "passive"))
      (node (ref "C24") (pin "2") (pinfunction "2_2") (pintype "passive"))
      (node (ref "C25") (pin "2") (pinfunction "2_2") (pintype "passive"))
      (node (ref "C26") (pin "2") (pinfunction "2_2") (pintype "passive"))
      (node (ref "C27") (pin "2") (pinfunction "2_2") (pintype "passive"))
      (node (ref "C28") (pin "2") (pinfunction "2_2") (pintype "passive"))
      (node (ref "C29") (pin "2") (pinfunction "2_2") (pintype "passive"))
      (node (ref "C3") (pin "2") (pinfunction "2_2") (pintype "passive"))
      (node (ref "C30") (pin "2") (pinfunction "2_2") (pintype "passive"))
      (node (ref "C31") (pin "2") (pinfunction "2_2") (pintype "passive"))
      (node (ref "C32") (pin "2") (pinfunction "2_2") (pintype "passive"))
      (node (ref "C33") (pin "2") (pinfunction "2_2") (pintype "passive"))
      (node (ref "C35") (pin "1") (pinfunction "1_1") (pintype "passive"))
      (node (ref "C36") (pin "2") (pinfunction "2_2") (pintype "passive"))
      (node (ref "C37") (pin "2") (pinfunction "2_2") (pintype "passive"))
      (node (ref "C38") (pin "1") (pinfunction "1_1") (pintype "passive"))
      (node (ref "C39") (pin "1") (pinfunction "1_1") (pintype "passive"))
      (node (ref "C40") (pin "1") (pinfunction "1_1") (pintype "passive"))
      (node (ref "C41") (pin "1") (pinfunction "1_1") (pintype "passive"))
      (node (ref "C42") (pin "2") (pinfunction "2_2") (pintype "passive"))
      (node (ref "C43") (pin "2") (pinfunction "2_2") (pintype "passive"))
      (node (ref "C44") (pin "2") (pinfunction "2_2") (pintype "passive"))
      (node (ref "C45") (pin "2") (pinfunction "2_2") (pintype "passive"))
      (node (ref "C46") (pin "2") (pinfunction "2_2") (pintype "passive"))
      (node (ref "C47") (pin "2") (pinfunction "2_2") (pintype "passive"))
      (node (ref "C48") (pin "2") (pinfunction "2_2") (pintype "passive"))
      (node (ref "C49") (pin "2") (pinfunction "2_2") (pintype "passive"))
      (node (ref "C5") (pin "2") (pinfunction "2_2") (pintype "passive"))
      (node (ref "C50") (pin "2") (pinfunction "2_2") (pintype "passive"))
      (node (ref "C51") (pin "2") (pinfunction "2_2") (pintype "passive"))
      (node (ref "C52") (pin "2") (pinfunction "2_2") (pintype "passive"))
      (node (ref "C53") (pin "2") (pinfunction "2_2") (pintype "passive"))
      (node (ref "C54") (pin "2") (pinfunction "2_2") (pintype "passive"))
      (node (ref "C55") (pin "2") (pinfunction "2_2") (pintype "passive"))
      (node (ref "C56") (pin "2") (pinfunction "2_2") (pintype "passive"))
      (node (ref "C57") (pin "2") (pinfunction "2_2") (pintype "passive"))
      (node (ref "C58") (pin "2") (pinfunction "2_2") (pintype "passive"))
      (node (ref "C59") (pin "2") (pinfunction "2_2") (pintype "passive"))
      (node (ref "C6") (pin "2") (pinfunction "2_2") (pintype "passive"))
      (node (ref "C60") (pin "2") (pinfunction "2_2") (pintype "passive"))
      (node (ref "C61") (pin "2") (pinfunction "2_2") (pintype "passive"))
      (node (ref "C62") (pin "2") (pinfunction "2_2") (pintype "passive"))
      (node (ref "C63") (pin "2") (pinfunction "2_2") (pintype "passive"))
      (node (ref "C64") (pin "2") (pinfunction "2_2") (pintype "passive"))
      (node (ref "C65") (pin "2") (pinfunction "2_2") (pintype "passive"))
      (node (ref "C66") (pin "2") (pinfunction "2_2") (pintype "passive"))
      (node (ref "C67") (pin "2") (pinfunction "2_2") (pintype "passive"))
      (node (ref "C68") (pin "2") (pinfunction "2_2") (pintype "passive"))
      (node (ref "C69") (pin "2") (pinfunction "2_2") (pintype "passive"))
      (node (ref "C7") (pin "2") (pinfunction "2_2") (pintype "passive"))
      (node (ref "C70") (pin "2") (pinfunction "2_2") (pintype "passive"))
      (node (ref "C71") (pin "2") (pinfunction "2_2") (pintype "passive"))
      (node (ref "C72") (pin "2") (pinfunction "2_2") (pintype "passive"))
      (node (ref "C73") (pin "2") (pinfunction "2_2") (pintype "passive"))
      (node (ref "C74") (pin "2") (pinfunction "2_2") (pintype "passive"))
      (node (ref "C75") (pin "2") (pinfunction "2_2") (pintype "passive"))
      (node (ref "C76") (pin "2") (pinfunction "2_2") (pintype "passive"))
      (node (ref "C77") (pin "2") (pinfunction "2_2") (pintype "passive"))
      (node (ref "C78") (pin "2") (pinfunction "2_2") (pintype "passive"))
      (node (ref "C79") (pin "2") (pinfunction "2_2") (pintype "passive"))
      (node (ref "C8") (pin "2") (pinfunction "2_2") (pintype "passive"))
      (node (ref "C80") (pin "2") (pinfunction "2_2") (pintype "passive"))
      (node (ref "C81") (pin "2") (pinfunction "2_2") (pintype "passive"))
      (node (ref "C82") (pin "2") (pinfunction "2_2") (pintype "passive"))
      (node (ref "C83") (pin "2") (pinfunction "2_2") (pintype "passive"))
      (node (ref "C84") (pin "2") (pinfunction "2_2") (pintype "passive"))
      (node (ref "C85") (pin "2") (pinfunction "2_2") (pintype "passive"))
      (node (ref "C86") (pin "1") (pinfunction "1_1") (pintype "passive"))
      (node (ref "C87") (pin "1") (pinfunction "1_1") (pintype "passive"))
      (node (ref "C88") (pin "2") (pinfunction "2_2") (pintype "passive"))
      (node (ref "C89") (pin "2") (pinfunction "2_2") (pintype "passive"))
      (node (ref "C9") (pin "2") (pinfunction "2_2") (pintype "passive"))
      (node (ref "C90") (pin "2") (pinfunction "2_2") (pintype "passive"))
      (node (ref "J1") (pin "BODY@1") (pinfunction "BODY_BODY@1") (pintype "bidirectional"))
      (node (ref "J1") (pin "BODY@2") (pinfunction "BODY_BODY@2") (pintype "bidirectional"))
      (node (ref "J1") (pin "BODY@3") (pinfunction "BODY_BODY@3") (pintype "bidirectional"))
      (node (ref "J1") (pin "BODY@4") (pinfunction "BODY_BODY@4") (pintype "bidirectional"))
      (node (ref "J1") (pin "P$6") (pinfunction "VSS_P$6") (pintype "bidirectional"))
      (node (ref "J2") (pin "GND") (pinfunction "GND_GND") (pintype "bidirectional"))
      (node (ref "J2") (pin "GNDBREAK") (pinfunction "GNDBREAK_GNDBREAK") (pintype "bidirectional"))
      (node (ref "J3") (pin "1") (pinfunction "GND_1") (pintype "bidirectional"))
      (node (ref "J3") (pin "10") (pinfunction "GND_10") (pintype "bidirectional"))
      (node (ref "J3") (pin "11") (pinfunction "GND_11") (pintype "bidirectional"))
      (node (ref "J3") (pin "14") (pinfunction "GND_14") (pintype "bidirectional"))
      (node (ref "J3") (pin "17") (pinfunction "GND_17") (pintype "bidirectional"))
      (node (ref "J3") (pin "20") (pinfunction "GND_20") (pintype "bidirectional"))
      (node (ref "J3") (pin "9") (pinfunction "RS1_9") (pintype "bidirectional"))
      (node (ref "J3") (pin "CGND@1") (pinfunction "CHASSIS_CGND@1") (pintype "bidirectional"))
      (node (ref "J3") (pin "CGND@11") (pinfunction "CHASSIS_CGND@11") (pintype "bidirectional"))
      (node (ref "J3") (pin "CGND@12") (pinfunction "CHASSIS_CGND@12") (pintype "bidirectional"))
      (node (ref "J3") (pin "CGND@13") (pinfunction "CHASSIS_CGND@13") (pintype "bidirectional"))
      (node (ref "J3") (pin "CGND@14") (pinfunction "CHASSIS_CGND@14") (pintype "bidirectional"))
      (node (ref "J3") (pin "CGND@15") (pinfunction "CHASSIS_CGND@15") (pintype "bidirectional"))
      (node (ref "J3") (pin "CGND@16") (pinfunction "CHASSIS_CGND@16") (pintype "bidirectional"))
      (node (ref "J3") (pin "CGND@19") (pinfunction "CHASSIS_CGND@19") (pintype "bidirectional"))
      (node (ref "J3") (pin "CGND@20") (pinfunction "CHASSIS_CGND@20") (pintype "bidirectional"))
      (node (ref "J3") (pin "CGND@6") (pinfunction "CHASSIS_CGND@6") (pintype "bidirectional"))
      (node (ref "J3") (pin "CGND@9") (pinfunction "CHASSIS_CGND@9") (pintype "bidirectional"))
      (node (ref "J4") (pin "P1_1") (pinfunction "P1_CT_CAP_P1_1") (pintype "bidirectional"))
      (node (ref "J4") (pin "P2_1") (pinfunction "P2_CT_CAP_P2_1") (pintype "bidirectional"))
      (node (ref "J4") (pin "P3_1") (pinfunction "P3_CT_CAP_P3_1") (pintype "bidirectional"))
      (node (ref "J4") (pin "P4_1") (pinfunction "P4_CT_CAP_P4_1") (pintype "bidirectional"))
      (node (ref "J4") (pin "SHIELD$1") (pinfunction "BDY_SHIELD$1") (pintype "bidirectional"))
      (node (ref "J4") (pin "SHIELD$5") (pinfunction "BDY_SHIELD$5") (pintype "bidirectional"))
      (node (ref "JP1") (pin "2") (pinfunction "2_2") (pintype "passive"))
      (node (ref "JP2") (pin "2") (pinfunction "2_2") (pintype "passive"))
      (node (ref "LED4") (pin "C") (pinfunction "C_C") (pintype "passive"))
      (node (ref "LED6") (pin "C") (pinfunction "C_C") (pintype "passive"))
      (node (ref "LED8") (pin "C") (pinfunction "C_C") (pintype "passive"))
      (node (ref "R10") (pin "2") (pinfunction "2_2") (pintype "passive"))
      (node (ref "R12") (pin "2") (pinfunction "2_2") (pintype "passive"))
      (node (ref "R15") (pin "2") (pinfunction "2_2") (pintype "passive"))
      (node (ref "R18") (pin "2") (pinfunction "2_2") (pintype "passive"))
      (node (ref "R19") (pin "2") (pinfunction "2_2") (pintype "passive"))
      (node (ref "R20") (pin "2") (pinfunction "2_2") (pintype "passive"))
      (node (ref "R21") (pin "2") (pinfunction "2_2") (pintype "passive"))
      (node (ref "R22") (pin "2") (pinfunction "2_2") (pintype "passive"))
      (node (ref "R23") (pin "2") (pinfunction "2_2") (pintype "passive"))
      (node (ref "R26") (pin "1") (pinfunction "1_1") (pintype "passive"))
      (node (ref "R6") (pin "2") (pinfunction "2_2") (pintype "passive"))
      (node (ref "SJ4") (pin "1") (pinfunction "1_1") (pintype "passive"))
      (node (ref "SJ5") (pin "1") (pinfunction "1_1") (pintype "passive"))
      (node (ref "SJ6") (pin "1") (pinfunction "1_1") (pintype "passive"))
      (node (ref "SJ7") (pin "1") (pinfunction "1_1") (pintype "passive"))
      (node (ref "U$1") (pin "P$1") (pinfunction "GND_P$1") (pintype "bidirectional"))
      (node (ref "U$1") (pin "P$13") (pinfunction "GND_P$13") (pintype "bidirectional"))
      (node (ref "U$1") (pin "P$14") (pinfunction "GND_P$14") (pintype "bidirectional"))
      (node (ref "U$1") (pin "P$2") (pinfunction "GND_P$2") (pintype "bidirectional"))
      (node (ref "U$1") (pin "P$22") (pinfunction "GND_P$22") (pintype "bidirectional"))
      (node (ref "U$1") (pin "P$23") (pinfunction "GND_P$23") (pintype "bidirectional"))
      (node (ref "U$1") (pin "P$32") (pinfunction "GND_P$32") (pintype "bidirectional"))
      (node (ref "U$1") (pin "P$33") (pinfunction "GND_P$33") (pintype "bidirectional"))
      (node (ref "U$1") (pin "P$42") (pinfunction "GND_P$42") (pintype "bidirectional"))
      (node (ref "U$1") (pin "P$43") (pinfunction "GND_P$43") (pintype "bidirectional"))
      (node (ref "U$1") (pin "P$52") (pinfunction "GND_P$52") (pintype "bidirectional"))
      (node (ref "U$1") (pin "P$53") (pinfunction "GND_P$53") (pintype "bidirectional"))
      (node (ref "U$1") (pin "P$59") (pinfunction "GND_P$59") (pintype "bidirectional"))
      (node (ref "U$1") (pin "P$60") (pinfunction "GND_P$60") (pintype "bidirectional"))
      (node (ref "U$1") (pin "P$65") (pinfunction "GND_P$65") (pintype "bidirectional"))
      (node (ref "U$1") (pin "P$66") (pinfunction "GND_P$66") (pintype "bidirectional"))
      (node (ref "U$1") (pin "P$7") (pinfunction "GND_P$7") (pintype "bidirectional"))
      (node (ref "U$1") (pin "P$71") (pinfunction "GND_P$71") (pintype "bidirectional"))
      (node (ref "U$1") (pin "P$74") (pinfunction "GND_P$74") (pintype "bidirectional"))
      (node (ref "U$1") (pin "P$8") (pinfunction "GND_P$8") (pintype "bidirectional"))
      (node (ref "U$1") (pin "P$98") (pinfunction "GND_P$98") (pintype "bidirectional"))
      (node (ref "U$2") (pin "5") (pinfunction "GND_5") (pintype "bidirectional"))
      (node (ref "U$2") (pin "BODY@1") (pinfunction "BODY_BODY@1") (pintype "bidirectional"))
      (node (ref "U$2") (pin "BODY@2") (pinfunction "BODY_BODY@2") (pintype "bidirectional"))
      (node (ref "U$2") (pin "BODY@3") (pinfunction "BODY_BODY@3") (pintype "bidirectional"))
      (node (ref "U$2") (pin "BODY@4") (pinfunction "BODY_BODY@4") (pintype "bidirectional"))
      (node (ref "U$2") (pin "BODY@5") (pinfunction "BODY_BODY@5") (pintype "bidirectional"))
      (node (ref "U$2") (pin "BODY@6") (pinfunction "BODY_BODY@6") (pintype "bidirectional"))
      (node (ref "U1") (pin "EP") (pinfunction "GND_EP") (pintype "bidirectional"))
      (node (ref "U1") (pin "P$7") (pinfunction "GND_P$7") (pintype "bidirectional"))
      (node (ref "U2") (pin "EP") (pinfunction "GND_EP") (pintype "bidirectional"))
      (node (ref "U2") (pin "P$7") (pinfunction "GND_P$7") (pintype "bidirectional"))
      (node (ref "U3") (pin "EP") (pinfunction "PAD_EP") (pintype "bidirectional"))
      (node (ref "U3") (pin "EP1") (pinfunction "PAD_EP1") (pintype "bidirectional"))
      (node (ref "U3") (pin "P$107") (pinfunction "GND_P$107") (pintype "bidirectional"))
      (node (ref "U3") (pin "P$109") (pinfunction "GND_P$109") (pintype "bidirectional"))
      (node (ref "U3") (pin "P$123") (pinfunction "GND_P$123") (pintype "bidirectional"))
      (node (ref "U3") (pin "P$46") (pinfunction "GND_P$46") (pintype "bidirectional"))
      (node (ref "U3") (pin "P$47") (pinfunction "GND_P$47") (pintype "bidirectional"))
      (node (ref "U3") (pin "P$69") (pinfunction "GND_P$69") (pintype "bidirectional"))
      (node (ref "U3") (pin "P$75") (pinfunction "GND_P$75") (pintype "bidirectional"))
      (node (ref "U3") (pin "P$77") (pinfunction "GND_P$77") (pintype "bidirectional"))
      (node (ref "U3") (pin "P$80") (pinfunction "GND_P$80") (pintype "bidirectional"))
      (node (ref "U4") (pin "16") (pinfunction "GND_16") (pintype "power_in"))
      (node (ref "U4") (pin "6") (pinfunction "GND_6") (pintype "power_in"))
      (node (ref "U5") (pin "EP") (pinfunction "GND_EP") (pintype "bidirectional"))
      (node (ref "U5") (pin "P$4") (pinfunction "GND_P$4") (pintype "bidirectional"))
      (node (ref "U6") (pin "EP") (pinfunction "GND_EP") (pintype "bidirectional"))
      (node (ref "U6") (pin "P$4") (pinfunction "GND_P$4") (pintype "bidirectional"))
    )
    (net (code "10") (name "Net-(C2-Pad1)") (class "Default")
      (node (ref "C2") (pin "1") (pinfunction "1_1") (pintype "passive"))
      (node (ref "R4") (pin "2") (pinfunction "2_2") (pintype "passive"))
    )
    (net (code "11") (name "Net-(C4-Pad2)") (class "Default")
      (node (ref "C4") (pin "2") (pinfunction "2_2") (pintype "passive"))
      (node (ref "R7") (pin "1") (pinfunction "1_1") (pintype "passive"))
    )
    (net (code "12") (name "Net-(C17-Pad1)") (class "Default")
      (node (ref "C17") (pin "1") (pinfunction "1_1") (pintype "passive"))
      (node (ref "R8") (pin "2") (pinfunction "2_2") (pintype "passive"))
    )
    (net (code "13") (name "Net-(C19-Pad2)") (class "Default")
      (node (ref "C19") (pin "2") (pinfunction "2_2") (pintype "passive"))
      (node (ref "R11") (pin "1") (pinfunction "1_1") (pintype "passive"))
    )
    (net (code "14") (name "Net-(C32-Pad1)") (class "Default")
      (node (ref "C32") (pin "1") (pinfunction "1_1") (pintype "passive"))
      (node (ref "J2") (pin "PWR") (pinfunction "PWR_PWR") (pintype "bidirectional"))
      (node (ref "Q1") (pin "5") (pinfunction "D_5") (pintype "bidirectional"))
      (node (ref "Q1") (pin "6") (pinfunction "D_6") (pintype "bidirectional"))
      (node (ref "Q1") (pin "7") (pinfunction "D_7") (pintype "bidirectional"))
      (node (ref "Q1") (pin "8") (pinfunction "D_8") (pintype "bidirectional"))
    )
    (net (code "15") (name "Net-(J3-RS0)") (class "Default")
      (node (ref "J3") (pin "7") (pinfunction "RS0_7") (pintype "bidirectional"))
      (node (ref "SJ11") (pin "1") (pinfunction "1_1") (pintype "passive"))
    )
    (net (code "16") (name "Net-(J3-RX_LOSS)") (class "Default")
      (node (ref "J3") (pin "8") (pinfunction "RX_LOSS_8") (pintype "bidirectional"))
      (node (ref "Q3") (pin "1") (pinfunction "G_1") (pintype "bidirectional"))
      (node (ref "R28") (pin "1") (pinfunction "1_1") (pintype "passive"))
    )
    (net (code "17") (name "Net-(J3-TX_DISABLE)") (class "Default")
      (node (ref "J3") (pin "3") (pinfunction "TX_DISABLE_3") (pintype "bidirectional"))
      (node (ref "R26") (pin "2") (pinfunction "2_2") (pintype "passive"))
    )
    (net (code "18") (name "Net-(J3-TX_FAULT)") (class "Default")
      (node (ref "J3") (pin "2") (pinfunction "TX_FAULT_2") (pintype "bidirectional"))
      (node (ref "R29") (pin "1") (pinfunction "1_1") (pintype "passive"))
    )
    (net (code "19") (name "Net-(J4-PadP1_GRN_A)") (class "Default")
      (node (ref "J4") (pin "P1_GRN_A") (pinfunction "P1_GRN_A_P1_GRN_A") (pintype "bidirectional"))
      (node (ref "R39") (pin "2") (pinfunction "2_2") (pintype "passive"))
    )
    (net (code "20") (name "Net-(J4-PadP1_YLW_A)") (class "Default")
      (node (ref "J4") (pin "P1_YLW_A") (pinfunction "P1_YLW_A_P1_YLW_A") (pintype "bidirectional"))
      (node (ref "R38") (pin "2") (pinfunction "2_2") (pintype "passive"))
    )
    (net (code "21") (name "Net-(J4-PadP2_GRN_A)") (class "Default")
      (node (ref "J4") (pin "P2_GRN_A") (pinfunction "P2_GRN_A_P2_GRN_A") (pintype "bidirectional"))
      (node (ref "R37") (pin "2") (pinfunction "2_2") (pintype "passive"))
    )
    (net (code "22") (name "Net-(J4-PadP2_YLW_A)") (class "Default")
      (node (ref "J4") (pin "P2_YLW_A") (pinfunction "P2_YLW_A_P2_YLW_A") (pintype "bidirectional"))
      (node (ref "R36") (pin "2") (pinfunction "2_2") (pintype "passive"))
    )
    (net (code "23") (name "Net-(J4-PadP3_GRN_A)") (class "Default")
      (node (ref "J4") (pin "P3_GRN_A") (pinfunction "P3_GRN_A_P3_GRN_A") (pintype "bidirectional"))
      (node (ref "R35") (pin "2") (pinfunction "2_2") (pintype "passive"))
    )
    (net (code "24") (name "Net-(J4-PadP3_YLW_A)") (class "Default")
      (node (ref "J4") (pin "P3_YLW_A") (pinfunction "P3_YLW_A_P3_YLW_A") (pintype "bidirectional"))
      (node (ref "R34") (pin "2") (pinfunction "2_2") (pintype "passive"))
    )
    (net (code "25") (name "Net-(J4-PadP4_GRN_A)") (class "Default")
      (node (ref "J4") (pin "P4_GRN_A") (pinfunction "P4_GRN_A_P4_GRN_A") (pintype "bidirectional"))
      (node (ref "R33") (pin "2") (pinfunction "2_2") (pintype "passive"))
    )
    (net (code "26") (name "Net-(J4-PadP4_YLW_A)") (class "Default")
      (node (ref "J4") (pin "P4_YLW_A") (pinfunction "P4_YLW_A_P4_YLW_A") (pintype "bidirectional"))
      (node (ref "R32") (pin "2") (pinfunction "2_2") (pintype "passive"))
    )
    (net (code "27") (name "Net-(L1-1)") (class "Default")
      (node (ref "L1") (pin "P$1") (pinfunction "1_P$1") (pintype "passive"))
      (node (ref "R7") (pin "2") (pinfunction "2_2") (pintype "passive"))
      (node (ref "U1") (pin "P$8") (pinfunction "SW_P$8") (pintype "bidirectional"))
    )
    (net (code "28") (name "Net-(L1-2)") (class "Default")
      (node (ref "C11") (pin "1") (pinfunction "1_1") (pintype "passive"))
      (node (ref "C12") (pin "1") (pinfunction "1_1") (pintype "passive"))
      (node (ref "C13") (pin "1") (pinfunction "1_1") (pintype "passive"))
      (node (ref "C14") (pin "1") (pinfunction "1_1") (pintype "passive"))
      (node (ref "C15") (pin "1") (pinfunction "1_1") (pintype "passive"))
      (node (ref "C16") (pin "1") (pinfunction "1_1") (pintype "passive"))
      (node (ref "L1") (pin "P$2") (pinfunction "2_P$2") (pintype "passive"))
      (node (ref "R5") (pin "1") (pinfunction "1_1") (pintype "passive"))
      (node (ref "SJ9") (pin "1") (pinfunction "1_1") (pintype "passive"))
    )
    (net (code "29") (name "Net-(L2-1)") (class "Default")
      (node (ref "L2") (pin "P$1") (pinfunction "1_P$1") (pintype "passive"))
      (node (ref "R11") (pin "2") (pinfunction "2_2") (pintype "passive"))
      (node (ref "U2") (pin "P$8") (pinfunction "SW_P$8") (pintype "bidirectional"))
    )
    (net (code "30") (name "Net-(L2-2)") (class "Default")
      (node (ref "C26") (pin "1") (pinfunction "1_1") (pintype "passive"))
      (node (ref "C27") (pin "1") (pinfunction "1_1") (pintype "passive"))
      (node (ref "C28") (pin "1") (pinfunction "1_1") (pintype "passive"))
      (node (ref "C29") (pin "1") (pinfunction "1_1") (pintype "passive"))
      (node (ref "C30") (pin "1") (pinfunction "1_1") (pintype "passive"))
      (node (ref "C31") (pin "1") (pinfunction "1_1") (pintype "passive"))
      (node (ref "L2") (pin "P$2") (pinfunction "2_P$2") (pintype "passive"))
      (node (ref "R9") (pin "1") (pinfunction "1_1") (pintype "passive"))
      (node (ref "SJ8") (pin "1") (pinfunction "1_1") (pintype "passive"))
    )
    (net (code "31") (name "Net-(LED1-PadC)") (class "Default")
      (node (ref "LED1") (pin "C") (pinfunction "C_C") (pintype "passive"))
      (node (ref "R1") (pin "1") (pinfunction "1_1") (pintype "passive"))
    )
    (net (code "32") (name "Net-(LED2-PadC)") (class "Default")
      (node (ref "LED2") (pin "C") (pinfunction "C_C") (pintype "passive"))
      (node (ref "R2") (pin "1") (pinfunction "1_1") (pintype "passive"))
    )
    (net (code "33") (name "Net-(LED3-PadC)") (class "Default")
      (node (ref "LED3") (pin "C") (pinfunction "C_C") (pintype "passive"))
      (node (ref "R3") (pin "1") (pinfunction "1_1") (pintype "passive"))
    )
    (net (code "34") (name "Net-(LED4-PadA)") (class "Default")
      (node (ref "LED4") (pin "A") (pinfunction "A_A") (pintype "passive"))
      (node (ref "R40") (pin "2") (pinfunction "2_2") (pintype "passive"))
    )
    (net (code "35") (name "Net-(LED5-PadA)") (class "Default")
      (node (ref "LED5") (pin "A") (pinfunction "A_A") (pintype "passive"))
      (node (ref "R41") (pin "2") (pinfunction "2_2") (pintype "passive"))
    )
    (net (code "36") (name "Net-(LED6-PadA)") (class "Default")
      (node (ref "LED6") (pin "A") (pinfunction "A_A") (pintype "passive"))
      (node (ref "R45") (pin "2") (pinfunction "2_2") (pintype "passive"))
    )
    (net (code "37") (name "Net-(LED7-PadA)") (class "Default")
      (node (ref "LED7") (pin "A") (pinfunction "A_A") (pintype "passive"))
      (node (ref "R42") (pin "2") (pinfunction "2_2") (pintype "passive"))
    )
    (net (code "38") (name "Net-(LED8-PadA)") (class "Default")
      (node (ref "LED8") (pin "A") (pinfunction "A_A") (pintype "passive"))
      (node (ref "R43") (pin "2") (pinfunction "2_2") (pintype "passive"))
    )
    (net (code "39") (name "Net-(Q1-G)") (class "Default")
      (node (ref "C34") (pin "2") (pinfunction "2_2") (pintype "passive"))
      (node (ref "Q1") (pin "4") (pinfunction "G_4") (pintype "bidirectional"))
      (node (ref "R12") (pin "1") (pinfunction "1_1") (pintype "passive"))
      (node (ref "Z1") (pin "1") (pinfunction "A_1") (pintype "passive"))
    )
    (net (code "40") (name "Net-(Q2-1)") (class "Default")
      (node (ref "C86") (pin "2") (pinfunction "2_2") (pintype "passive"))
      (node (ref "Q2") (pin "P$1") (pinfunction "1_P$1") (pintype "passive"))
      (node (ref "U3") (pin "P$126") (pinfunction "X1_P$126") (pintype "bidirectional"))
    )
    (net (code "41") (name "Net-(Q2-2)") (class "Default")
      (node (ref "C85") (pin "1") (pinfunction "1_1") (pintype "passive"))
      (node (ref "Q2") (pin "P$3") (pinfunction "2_P$3") (pintype "passive"))
      (node (ref "U3") (pin "P$125") (pinfunction "X0_P$125") (pintype "bidirectional"))
    )
    (net (code "42") (name "Net-(Q3-D)") (class "Default")
      (node (ref "Q3") (pin "3") (pinfunction "D_3") (pintype "bidirectional"))
      (node (ref "R45") (pin "1") (pinfunction "1_1") (pintype "passive"))
    )
    (net (code "43") (name "Net-(R27-Pad1)") (class "Default")
      (node (ref "R27") (pin "1") (pinfunction "1_1") (pintype "passive"))
      (node (ref "SJ11") (pin "2") (pinfunction "2_2") (pintype "passive"))
    )
    (net (code "44") (name "Net-(T1-MCT1)") (class "Default")
      (node (ref "C42") (pin "1") (pinfunction "1_1") (pintype "passive"))
      (node (ref "T1") (pin "P$24") (pinfunction "MCT1_P$24") (pintype "bidirectional"))
    )
    (net (code "45") (name "Net-(T1-MCT2)") (class "Default")
      (node (ref "C43") (pin "1") (pinfunction "1_1") (pintype "passive"))
      (node (ref "T1") (pin "P$21") (pinfunction "MCT2_P$21") (pintype "bidirectional"))
    )
    (net (code "46") (name "Net-(T1-MCT3)") (class "Default")
      (node (ref "C44") (pin "1") (pinfunction "1_1") (pintype "passive"))
      (node (ref "T1") (pin "P$18") (pinfunction "MCT3_P$18") (pintype "bidirectional"))
    )
    (net (code "47") (name "Net-(T1-MCT4)") (class "Default")
      (node (ref "C45") (pin "1") (pinfunction "1_1") (pintype "passive"))
      (node (ref "T1") (pin "P$15") (pinfunction "MCT4_P$15") (pintype "bidirectional"))
    )
    (net (code "48") (name "Net-(T1-TCT1)") (class "Default")
      (node (ref "C38") (pin "2") (pinfunction "2_2") (pintype "passive"))
      (node (ref "T1") (pin "P$1") (pinfunction "TCT1_P$1") (pintype "bidirectional"))
    )
    (net (code "49") (name "Net-(T1-TCT2)") (class "Default")
      (node (ref "C39") (pin "2") (pinfunction "2_2") (pintype "passive"))
      (node (ref "T1") (pin "P$4") (pinfunction "TCT2_P$4") (pintype "bidirectional"))
    )
    (net (code "50") (name "Net-(T1-TCT3)") (class "Default")
      (node (ref "C40") (pin "2") (pinfunction "2_2") (pintype "passive"))
      (node (ref "T1") (pin "P$7") (pinfunction "TCT3_P$7") (pintype "bidirectional"))
    )
    (net (code "51") (name "Net-(T1-TCT4)") (class "Default")
      (node (ref "C41") (pin "2") (pinfunction "2_2") (pintype "passive"))
      (node (ref "T1") (pin "P$10") (pinfunction "TCT4_P$10") (pintype "bidirectional"))
    )
    (net (code "52") (name "Net-(U$1-BT_NDSBL)") (class "Default")
      (node (ref "SJ5") (pin "2") (pinfunction "2_2") (pintype "passive"))
      (node (ref "U$1") (pin "P$91") (pinfunction "BT_NDSBL_P$91") (pintype "bidirectional"))
    )
    (net (code "53") (name "Net-(U$1-ETH_NLED2)") (class "Default")
      (node (ref "R2") (pin "2") (pinfunction "2_2") (pintype "passive"))
      (node (ref "U$1") (pin "P$17") (pinfunction "ETH_NLED2_P$17") (pintype "bidirectional"))
    )
    (net (code "54") (name "Net-(U$1-ETH_NLED3)") (class "Default")
      (node (ref "R3") (pin "2") (pinfunction "2_2") (pintype "passive"))
      (node (ref "U$1") (pin "P$15") (pinfunction "ETH_NLED3_P$15") (pintype "bidirectional"))
    )
    (net (code "55") (name "Net-(U$1-GLOBAL_EN)") (class "Default")
      (node (ref "SJ7") (pin "2") (pinfunction "2_2") (pintype "passive"))
      (node (ref "U$1") (pin "P$99") (pinfunction "GLOBAL_EN_P$99") (pintype "bidirectional"))
    )
    (net (code "56") (name "Net-(U$1-GPIO_VREF)") (class "Default")
      (node (ref "SJ2") (pin "1") (pinfunction "1_1") (pintype "passive"))
      (node (ref "SJ3") (pin "1") (pinfunction "1_1") (pintype "passive"))
      (node (ref "U$1") (pin "P$78") (pinfunction "GPIO_VREF_P$78") (pintype "bidirectional"))
    )
    (net (code "57") (name "Net-(U$1-NRPIBOOT)") (class "Default")
      (node (ref "SJ6") (pin "2") (pinfunction "2_2") (pintype "passive"))
      (node (ref "U$1") (pin "P$93") (pinfunction "NRPIBOOT_P$93") (pintype "bidirectional"))
    )
    (net (code "58") (name "Net-(U$1-PI_NLED_ACT)") (class "Default")
      (node (ref "R1") (pin "2") (pinfunction "2_2") (pintype "passive"))
      (node (ref "U$1") (pin "P$21") (pinfunction "PI_NLED_ACT_P$21") (pintype "bidirectional"))
    )
    (net (code "59") (name "Net-(U$1-WL_NDSBL)") (class "Default")
      (node (ref "SJ4") (pin "2") (pinfunction "2_2") (pintype "passive"))
      (node (ref "U$1") (pin "P$89") (pinfunction "WL_NDSBL_P$89") (pintype "bidirectional"))
    )
    (net (code "60") (name "Net-(U$2-D+)") (class "Default")
      (node (ref "R14") (pin "1") (pinfunction "1_1") (pintype "passive"))
      (node (ref "U$2") (pin "3") (pinfunction "D+_3") (pintype "bidirectional"))
    )
    (net (code "61") (name "Net-(U$2-D-)") (class "Default")
      (node (ref "R13") (pin "1") (pinfunction "1_1") (pintype "passive"))
      (node (ref "U$2") (pin "2") (pinfunction "D-_2") (pintype "bidirectional"))
    )
    (net (code "62") (name "Net-(U1-BST)") (class "Default")
      (node (ref "C4") (pin "1") (pinfunction "1_1") (pintype "passive"))
      (node (ref "U1") (pin "P$1") (pinfunction "BST_P$1") (pintype "bidirectional"))
    )
    (net (code "63") (name "Net-(U1-COMP)") (class "Default")
      (node (ref "R4") (pin "1") (pinfunction "1_1") (pintype "passive"))
      (node (ref "U1") (pin "P$6") (pinfunction "COMP_P$6") (pintype "bidirectional"))
    )
    (net (code "64") (name "Net-(U1-FB)") (class "Default")
      (node (ref "R5") (pin "2") (pinfunction "2_2") (pintype "passive"))
      (node (ref "R6") (pin "1") (pinfunction "1_1") (pintype "passive"))
      (node (ref "U1") (pin "P$5") (pinfunction "FB_P$5") (pintype "bidirectional"))
    )
    (net (code "65") (name "Net-(U1-SS)") (class "Default")
      (node (ref "C3") (pin "1") (pinfunction "1_1") (pintype "passive"))
      (node (ref "U1") (pin "P$4") (pinfunction "SS_P$4") (pintype "bidirectional"))
    )
    (net (code "66") (name "Net-(U2-BST)") (class "Default")
      (node (ref "C19") (pin "1") (pinfunction "1_1") (pintype "passive"))
      (node (ref "U2") (pin "P$1") (pinfunction "BST_P$1") (pintype "bidirectional"))
    )
    (net (code "67") (name "Net-(U2-COMP)") (class "Default")
      (node (ref "R8") (pin "1") (pinfunction "1_1") (pintype "passive"))
      (node (ref "U2") (pin "P$6") (pinfunction "COMP_P$6") (pintype "bidirectional"))
    )
    (net (code "68") (name "Net-(U2-FB)") (class "Default")
      (node (ref "R10") (pin "1") (pinfunction "1_1") (pintype "passive"))
      (node (ref "R9") (pin "2") (pinfunction "2_2") (pintype "passive"))
      (node (ref "U2") (pin "P$5") (pinfunction "FB_P$5") (pintype "bidirectional"))
    )
    (net (code "69") (name "Net-(U2-SS)") (class "Default")
      (node (ref "C18") (pin "1") (pinfunction "1_1") (pintype "passive"))
      (node (ref "U2") (pin "P$4") (pinfunction "SS_P$4") (pintype "bidirectional"))
    )
    (net (code "70") (name "Net-(U3-IBA)") (class "Default")
      (node (ref "SJ10") (pin "1") (pinfunction "1_1") (pintype "passive"))
      (node (ref "U3") (pin "P$67") (pinfunction "IBA_P$67") (pintype "bidirectional"))
    )
    (net (code "71") (name "Net-(U3-INTRP_N)") (class "Default")
      (node (ref "R24") (pin "1") (pinfunction "1_1") (pintype "passive"))
      (node (ref "U3") (pin "P$94") (pinfunction "INTRP_N_P$94") (pintype "bidirectional"))
    )
    (net (code "72") (name "Net-(U3-ISET)") (class "Default")
      (node (ref "R15") (pin "1") (pinfunction "1_1") (pintype "passive"))
      (node (ref "U3") (pin "P$127") (pinfunction "ISET_P$127") (pintype "bidirectional"))
    )
    (net (code "73") (name "Net-(U3-RXD6_0)") (class "Default")
      (node (ref "R18") (pin "1") (pinfunction "1_1") (pintype "passive"))
      (node (ref "U3") (pin "P$65") (pinfunction "RXD6_0_P$65") (pintype "bidirectional"))
    )
    (net (code "74") (name "Net-(U3-RXD6_1)") (class "Default")
      (node (ref "R19") (pin "1") (pinfunction "1_1") (pintype "passive"))
      (node (ref "U3") (pin "P$64") (pinfunction "RXD6_1_P$64") (pintype "bidirectional"))
    )
    (net (code "75") (name "Net-(U3-RXD6_2)") (class "Default")
      (node (ref "R20") (pin "1") (pinfunction "1_1") (pintype "passive"))
      (node (ref "U3") (pin "P$63") (pinfunction "RXD6_2_P$63") (pintype "bidirectional"))
    )
    (net (code "76") (name "Net-(U3-RXD6_3)") (class "Default")
      (node (ref "R21") (pin "1") (pinfunction "1_1") (pintype "passive"))
      (node (ref "U3") (pin "P$62") (pinfunction "RXD6_3_P$62") (pintype "bidirectional"))
    )
    (net (code "77") (name "Net-(U3-SYNCLKO)") (class "Default")
      (node (ref "R25") (pin "1") (pinfunction "1_1") (pintype "passive"))
      (node (ref "U3") (pin "P$95") (pinfunction "SYNCLKO_P$95") (pintype "bidirectional"))
    )
    (net (code "78") (name "Net-(U3-S_REXT)") (class "Default")
      (node (ref "R22") (pin "1") (pinfunction "1_1") (pintype "passive"))
      (node (ref "U3") (pin "P$76") (pinfunction "S_REXT_P$76") (pintype "bidirectional"))
    )
    (net (code "79") (name "Net-(U4-RXLED)") (class "Default")
      (node (ref "LED7") (pin "C") (pinfunction "C_C") (pintype "passive"))
      (node (ref "U4") (pin "17") (pinfunction "RXLED_17") (pintype "input"))
    )
    (net (code "80") (name "Net-(U4-TXLED)") (class "Default")
      (node (ref "LED5") (pin "C") (pinfunction "C_C") (pintype "passive"))
      (node (ref "U4") (pin "10") (pinfunction "TXLED_10") (pintype "input"))
    )
    (net (code "81") (name "Net-(U4-USBDM)") (class "Default")
      (node (ref "R13") (pin "2") (pinfunction "2_2") (pintype "passive"))
      (node (ref "U4") (pin "12") (pinfunction "USBDM_12") (pintype "bidirectional"))
    )
    (net (code "82") (name "Net-(U4-USBDP)") (class "Default")
      (node (ref "R14") (pin "2") (pinfunction "2_2") (pintype "passive"))
      (node (ref "U4") (pin "11") (pinfunction "USBDP_11") (pintype "bidirectional"))
    )
    (net (code "83") (name "P1_LED0") (class "Default")
      (node (ref "J4") (pin "P1_YLW_C") (pinfunction "P1_YLW_C_P1_YLW_C") (pintype "bidirectional"))
      (node (ref "U3") (pin "P$105") (pinfunction "LED1_0_P$105") (pintype "bidirectional"))
    )
    (net (code "84") (name "P1_LED1") (class "Default")
      (node (ref "J4") (pin "P1_GRN_C") (pinfunction "P1_GRN_C_P1_GRN_C") (pintype "bidirectional"))
      (node (ref "U3") (pin "P$106") (pinfunction "LED1_1_P$106") (pintype "bidirectional"))
    )
    (net (code "85") (name "P2_LED0") (class "Default")
      (node (ref "J4") (pin "P2_YLW_C") (pinfunction "P2_YLW_C_P2_YLW_C") (pintype "bidirectional"))
      (node (ref "U3") (pin "P$91") (pinfunction "LED2_0_P$91") (pintype "bidirectional"))
    )
    (net (code "86") (name "P2_LED1") (class "Default")
      (node (ref "J4") (pin "P2_GRN_C") (pinfunction "P2_GRN_C_P2_GRN_C") (pintype "bidirectional"))
      (node (ref "U3") (pin "P$92") (pinfunction "LED2_1_P$92") (pintype "bidirectional"))
    )
    (net (code "87") (name "P3_LED0") (class "Default")
      (node (ref "J4") (pin "P3_YLW_C") (pinfunction "P3_YLW_C_P3_YLW_C") (pintype "bidirectional"))
      (node (ref "U3") (pin "P$88") (pinfunction "LED3_0_P$88") (pintype "bidirectional"))
    )
    (net (code "88") (name "P3_LED1") (class "Default")
      (node (ref "J4") (pin "P3_GRN_C") (pinfunction "P3_GRN_C_P3_GRN_C") (pintype "bidirectional"))
      (node (ref "U3") (pin "P$89") (pinfunction "LED3_1_P$89") (pintype "bidirectional"))
    )
    (net (code "89") (name "P4_LED0") (class "Default")
      (node (ref "J4") (pin "P4_YLW_C") (pinfunction "P4_YLW_C_P4_YLW_C") (pintype "bidirectional"))
      (node (ref "U3") (pin "P$85") (pinfunction "LED4_0_P$85") (pintype "bidirectional"))
    )
    (net (code "90") (name "P4_LED1") (class "Default")
      (node (ref "J4") (pin "P4_GRN_C") (pinfunction "P4_GRN_C_P4_GRN_C") (pintype "bidirectional"))
      (node (ref "U3") (pin "P$86") (pinfunction "LED4_1_P$86") (pintype "bidirectional"))
    )
    (net (code "91") (name "PI_ETH_P0_N") (class "Default")
      (node (ref "T1") (pin "P$3") (pinfunction "TD1-_P$3") (pintype "bidirectional"))
      (node (ref "U$1") (pin "P$10") (pinfunction "ETH_P0_N_P$10") (pintype "bidirectional"))
    )
    (net (code "92") (name "PI_ETH_P0_P") (class "Default")
      (node (ref "T1") (pin "P$2") (pinfunction "TD1+_P$2") (pintype "bidirectional"))
      (node (ref "U$1") (pin "P$12") (pinfunction "ETH_P0_P_P$12") (pintype "bidirectional"))
    )
    (net (code "93") (name "PI_ETH_P1_N") (class "Default")
      (node (ref "T1") (pin "P$6") (pinfunction "TD2-_P$6") (pintype "bidirectional"))
      (node (ref "U$1") (pin "P$6") (pinfunction "ETH_P1_N_P$6") (pintype "bidirectional"))
    )
    (net (code "94") (name "PI_ETH_P1_P") (class "Default")
      (node (ref "T1") (pin "P$5") (pinfunction "TD2+_P$5") (pintype "bidirectional"))
      (node (ref "U$1") (pin "P$4") (pinfunction "ETH_P1_P_P$4") (pintype "bidirectional"))
    )
    (net (code "95") (name "PI_ETH_P2_N") (class "Default")
      (node (ref "T1") (pin "P$9") (pinfunction "TD3-_P$9") (pintype "bidirectional"))
      (node (ref "U$1") (pin "P$9") (pinfunction "ETH_P2_N_P$9") (pintype "bidirectional"))
    )
    (net (code "96") (name "PI_ETH_P2_P") (class "Default")
      (node (ref "T1") (pin "P$8") (pinfunction "TD3+_P$8") (pintype "bidirectional"))
      (node (ref "U$1") (pin "P$11") (pinfunction "ETH_P2_P_P$11") (pintype "bidirectional"))
    )
    (net (code "97") (name "PI_ETH_P3_N") (class "Default")
      (node (ref "T1") (pin "P$12") (pinfunction "TD4-_P$12") (pintype "bidirectional"))
      (node (ref "U$1") (pin "P$5") (pinfunction "ETH_P3_N_P$5") (pintype "bidirectional"))
    )
    (net (code "98") (name "PI_ETH_P3_P") (class "Default")
      (node (ref "T1") (pin "P$11") (pinfunction "TD4+_P$11") (pintype "bidirectional"))
      (node (ref "U$1") (pin "P$3") (pinfunction "ETH_P3_P_P$3") (pintype "bidirectional"))
    )
    (net (code "99") (name "PI_EXTRST") (class "Default")
      (node (ref "C87") (pin "2") (pinfunction "2_2") (pintype "passive"))
      (node (ref "R23") (pin "1") (pinfunction "1_1") (pintype "passive"))
      (node (ref "R44") (pin "1") (pinfunction "1_1") (pintype "passive"))
      (node (ref "U$1") (pin "P$100") (pinfunction "NEXTRST_P$100") (pintype "bidirectional"))
      (node (ref "U3") (pin "P$96") (pinfunction "RESET_N_P$96") (pintype "bidirectional"))
    )
    (net (code "100") (name "RPI_1V8") (class "Default")
      (node (ref "SJ3") (pin "2") (pinfunction "2_2") (pintype "passive"))
      (node (ref "U$1") (pin "P$88") (pinfunction "CM4_1V8_OUT_P$88") (pintype "bidirectional"))
      (node (ref "U$1") (pin "P$90") (pinfunction "CM4_1V8_OUT_P$90") (pintype "bidirectional"))
    )
    (net (code "101") (name "RPI_3V3") (class "Default")
      (node (ref "LED1") (pin "A") (pinfunction "A_A") (pintype "passive"))
      (node (ref "LED2") (pin "A") (pinfunction "A_A") (pintype "passive"))
      (node (ref "LED3") (pin "A") (pinfunction "A_A") (pintype "passive"))
      (node (ref "SJ1") (pin "1") (pinfunction "1_1") (pintype "passive"))
      (node (ref "SJ2") (pin "2") (pinfunction "2_2") (pintype "passive"))
      (node (ref "U$1") (pin "P$84") (pinfunction "CM4_3V3_OUT_P$84") (pintype "bidirectional"))
      (node (ref "U$1") (pin "P$86") (pinfunction "CM4_3V3_OUT_P$86") (pintype "bidirectional"))
    )
    (net (code "102") (name "RPI_SCL0") (class "Default")
      (node (ref "J3") (pin "5") (pinfunction "SCL_5") (pintype "bidirectional"))
      (node (ref "R31") (pin "2") (pinfunction "2_2") (pintype "passive"))
      (node (ref "U$1") (pin "P$80") (pinfunction "SCL0_P$80") (pintype "bidirectional"))
    )
    (net (code "103") (name "RPI_SDA0") (class "Default")
      (node (ref "J3") (pin "4") (pinfunction "SDA_4") (pintype "bidirectional"))
      (node (ref "R30") (pin "2") (pinfunction "2_2") (pintype "passive"))
      (node (ref "U$1") (pin "P$82") (pinfunction "SDA0_P$82") (pintype "bidirectional"))
    )
    (net (code "104") (name "SD_3V3") (class "Default")
      (node (ref "C1") (pin "2") (pinfunction "2_2") (pintype "passive"))
      (node (ref "J1") (pin "P$4") (pinfunction "VDD_P$4") (pintype "bidirectional"))
      (node (ref "SJ1") (pin "2") (pinfunction "2_2") (pintype "passive"))
    )
    (net (code "105") (name "SD_CLK") (class "Default")
      (node (ref "J1") (pin "P$5") (pinfunction "CLK_P$5") (pintype "bidirectional"))
      (node (ref "U$1") (pin "P$57") (pinfunction "SD_CLK_P$57") (pintype "bidirectional"))
    )
    (net (code "106") (name "SD_CMD") (class "Default")
      (node (ref "J1") (pin "P$3") (pinfunction "CMD_P$3") (pintype "bidirectional"))
      (node (ref "U$1") (pin "P$62") (pinfunction "SD_CMD_P$62") (pintype "bidirectional"))
    )
    (net (code "107") (name "SD_DAT0") (class "Default")
      (node (ref "J1") (pin "P$7") (pinfunction "DAT0_P$7") (pintype "bidirectional"))
      (node (ref "U$1") (pin "P$63") (pinfunction "SD_DAT0_P$63") (pintype "bidirectional"))
    )
    (net (code "108") (name "SD_DAT1") (class "Default")
      (node (ref "J1") (pin "P$8") (pinfunction "DAT1_P$8") (pintype "bidirectional"))
      (node (ref "U$1") (pin "P$67") (pinfunction "SD_DAT1_P$67") (pintype "bidirectional"))
    )
    (net (code "109") (name "SD_DAT2") (class "Default")
      (node (ref "J1") (pin "P$1") (pinfunction "DAT2_P$1") (pintype "bidirectional"))
      (node (ref "U$1") (pin "P$69") (pinfunction "SD_DAT2_P$69") (pintype "bidirectional"))
    )
    (net (code "110") (name "SD_DAT3") (class "Default")
      (node (ref "J1") (pin "P$2") (pinfunction "DAT3_P$2") (pintype "bidirectional"))
      (node (ref "U$1") (pin "P$61") (pinfunction "SD_DAT3_P$61") (pintype "bidirectional"))
    )
    (net (code "111") (name "SFP_VCCRX") (class "Default")
      (node (ref "C90") (pin "1") (pinfunction "1_1") (pintype "passive"))
      (node (ref "FB7") (pin "2") (pinfunction "2_2") (pintype "passive"))
      (node (ref "J3") (pin "15") (pinfunction "VCCRX_15") (pintype "bidirectional"))
    )
    (net (code "112") (name "SFP_VCCTX") (class "Default")
      (node (ref "C88") (pin "1") (pinfunction "1_1") (pintype "passive"))
      (node (ref "C89") (pin "1") (pinfunction "1_1") (pintype "passive"))
      (node (ref "FB6") (pin "2") (pinfunction "2_2") (pintype "passive"))
      (node (ref "J3") (pin "16") (pinfunction "VCCTX_16") (pintype "bidirectional"))
    )
    (net (code "113") (name "SPI0_CE0") (class "Default")
      (node (ref "R17") (pin "1") (pinfunction "1_1") (pintype "passive"))
      (node (ref "U$1") (pin "P$39") (pinfunction "GPIO8_P$39") (pintype "bidirectional"))
      (node (ref "U3") (pin "P$100") (pinfunction "SCS_P$100") (pintype "bidirectional"))
    )
    (net (code "114") (name "SPI0_CE1") (class "Default")
      (node (ref "U$1") (pin "P$37") (pinfunction "GPIO7_P$37") (pintype "bidirectional"))
    )
    (net (code "115") (name "SPI0_CLK") (class "Default")
      (node (ref "U$1") (pin "P$38") (pinfunction "GPIO11_P$38") (pintype "bidirectional"))
      (node (ref "U3") (pin "P$101") (pinfunction "CLK_P$101") (pintype "bidirectional"))
    )
    (net (code "116") (name "SPI0_MISO") (class "Default")
      (node (ref "U$1") (pin "P$40") (pinfunction "GPIO9_P$40") (pintype "bidirectional"))
      (node (ref "U3") (pin "P$97") (pinfunction "MISO_P$97") (pintype "bidirectional"))
    )
    (net (code "117") (name "SPI0_MOSI") (class "Default")
      (node (ref "R16") (pin "1") (pinfunction "1_1") (pintype "passive"))
      (node (ref "U$1") (pin "P$44") (pinfunction "GPIO10_P$44") (pintype "bidirectional"))
      (node (ref "U3") (pin "P$98") (pinfunction "MOSI_P$98") (pintype "bidirectional"))
    )
    (net (code "118") (name "SYS_ACT") (class "Default")
      (node (ref "R43") (pin "1") (pinfunction "1_1") (pintype "passive"))
      (node (ref "U$1") (pin "P$25") (pinfunction "GPIO21_P$25") (pintype "bidirectional"))
    )
    (net (code "119") (name "S_RX7_N") (class "Default")
      (node (ref "J3") (pin "19") (pinfunction "TX1N_19") (pintype "bidirectional"))
      (node (ref "U3") (pin "P$82") (pinfunction "S_OUT7M_P$82") (pintype "bidirectional"))
    )
    (net (code "120") (name "S_RX7_P") (class "Default")
      (node (ref "J3") (pin "18") (pinfunction "TX1P_18") (pintype "bidirectional"))
      (node (ref "U3") (pin "P$81") (pinfunction "S_OUT7P_P$81") (pintype "bidirectional"))
    )
    (net (code "121") (name "S_TX7_N") (class "Default")
      (node (ref "J3") (pin "12") (pinfunction "RX1N_12") (pintype "bidirectional"))
      (node (ref "U3") (pin "P$78") (pinfunction "S_IN7M_P$78") (pintype "bidirectional"))
    )
    (net (code "122") (name "S_TX7_P") (class "Default")
      (node (ref "J3") (pin "13") (pinfunction "RX1P_13") (pintype "bidirectional"))
      (node (ref "U3") (pin "P$79") (pinfunction "S_IN7P_P$79") (pintype "bidirectional"))
    )
    (net (code "123") (name "TXRX1M_A") (class "Default")
      (node (ref "J4") (pin "P1_3") (pinfunction "P1_TRD1-_P1_3") (pintype "bidirectional"))
      (node (ref "U3") (pin "P$2") (pinfunction "TXRX1M_A_P$2") (pintype "bidirectional"))
    )
    (net (code "124") (name "TXRX1M_B") (class "Default")
      (node (ref "J4") (pin "P1_5") (pinfunction "P1_TRD2-_P1_5") (pintype "bidirectional"))
      (node (ref "U3") (pin "P$5") (pinfunction "TXRX1M_B_P$5") (pintype "bidirectional"))
    )
    (net (code "125") (name "TXRX1M_C") (class "Default")
      (node (ref "J4") (pin "P1_7") (pinfunction "P1_TRD3-_P1_7") (pintype "bidirectional"))
      (node (ref "U3") (pin "P$7") (pinfunction "TXRX1M_C_P$7") (pintype "bidirectional"))
    )
    (net (code "126") (name "TXRX1M_D") (class "Default")
      (node (ref "J4") (pin "P1_9") (pinfunction "P1_TRD4-_P1_9") (pintype "bidirectional"))
      (node (ref "U3") (pin "P$9") (pinfunction "TXRX1M_D_P$9") (pintype "bidirectional"))
    )
    (net (code "127") (name "TXRX1P_A") (class "Default")
      (node (ref "J4") (pin "P1_2") (pinfunction "P1_TRD1+_P1_2") (pintype "bidirectional"))
      (node (ref "U3") (pin "P$1") (pinfunction "TXRX1P_A_P$1") (pintype "bidirectional"))
    )
    (net (code "128") (name "TXRX1P_B") (class "Default")
      (node (ref "J4") (pin "P1_4") (pinfunction "P1_TRD2+_P1_4") (pintype "bidirectional"))
      (node (ref "U3") (pin "P$4") (pinfunction "TXRX1P_B_P$4") (pintype "bidirectional"))
    )
    (net (code "129") (name "TXRX1P_C") (class "Default")
      (node (ref "J4") (pin "P1_6") (pinfunction "P1_TRD3+_P1_6") (pintype "bidirectional"))
      (node (ref "U3") (pin "P$6") (pinfunction "TXRX1P_C_P$6") (pintype "bidirectional"))
    )
    (net (code "130") (name "TXRX1P_D") (class "Default")
      (node (ref "J4") (pin "P1_8") (pinfunction "P1_TRD4+_P1_8") (pintype "bidirectional"))
      (node (ref "U3") (pin "P$8") (pinfunction "TXRX1P_D_P$8") (pintype "bidirectional"))
    )
    (net (code "131") (name "TXRX2M_A") (class "Default")
      (node (ref "J4") (pin "P2_3") (pinfunction "P2_TRD1-_P2_3") (pintype "bidirectional"))
      (node (ref "U3") (pin "P$13") (pinfunction "TXRX2M_A_P$13") (pintype "bidirectional"))
    )
    (net (code "132") (name "TXRX2M_B") (class "Default")
      (node (ref "J4") (pin "P2_5") (pinfunction "P2_TRD2-_P2_5") (pintype "bidirectional"))
      (node (ref "U3") (pin "P$16") (pinfunction "TXRX2M_B_P$16") (pintype "bidirectional"))
    )
    (net (code "133") (name "TXRX2M_C") (class "Default")
      (node (ref "J4") (pin "P2_7") (pinfunction "P2_TRD3-_P2_7") (pintype "bidirectional"))
      (node (ref "U3") (pin "P$18") (pinfunction "TXRX2M_C_P$18") (pintype "bidirectional"))
    )
    (net (code "134") (name "TXRX2M_D") (class "Default")
      (node (ref "J4") (pin "P2_9") (pinfunction "P2_TRD4-_P2_9") (pintype "bidirectional"))
      (node (ref "U3") (pin "P$21") (pinfunction "TXRX2M_D_P$21") (pintype "bidirectional"))
    )
    (net (code "135") (name "TXRX2P_A") (class "Default")
      (node (ref "J4") (pin "P2_2") (pinfunction "P2_TRD1+_P2_2") (pintype "bidirectional"))
      (node (ref "U3") (pin "P$12") (pinfunction "TXRX2P_A_P$12") (pintype "bidirectional"))
    )
    (net (code "136") (name "TXRX2P_B") (class "Default")
      (node (ref "J4") (pin "P2_4") (pinfunction "P2_TRD2+_P2_4") (pintype "bidirectional"))
      (node (ref "U3") (pin "P$15") (pinfunction "TXRX2P_B_P$15") (pintype "bidirectional"))
    )
    (net (code "137") (name "TXRX2P_C") (class "Default")
      (node (ref "J4") (pin "P2_6") (pinfunction "P2_TRD3+_P2_6") (pintype "bidirectional"))
      (node (ref "U3") (pin "P$17") (pinfunction "TXRX2P_C_P$17") (pintype "bidirectional"))
    )
    (net (code "138") (name "TXRX2P_D") (class "Default")
      (node (ref "J4") (pin "P2_8") (pinfunction "P2_TRD4+_P2_8") (pintype "bidirectional"))
      (node (ref "U3") (pin "P$20") (pinfunction "TXRX2P_D_P$20") (pintype "bidirectional"))
    )
    (net (code "139") (name "TXRX3M_A") (class "Default")
      (node (ref "J4") (pin "P3_3") (pinfunction "P3_TRD1-_P3_3") (pintype "bidirectional"))
      (node (ref "U3") (pin "P$25") (pinfunction "TXRX3M_A_P$25") (pintype "bidirectional"))
    )
    (net (code "140") (name "TXRX3M_B") (class "Default")
      (node (ref "J4") (pin "P3_5") (pinfunction "P3_TRD2-_P3_5") (pintype "bidirectional"))
      (node (ref "U3") (pin "P$27") (pinfunction "TXRX3M_B_P$27") (pintype "bidirectional"))
    )
    (net (code "141") (name "TXRX3M_C") (class "Default")
      (node (ref "J4") (pin "P3_7") (pinfunction "P3_TRD3-_P3_7") (pintype "bidirectional"))
      (node (ref "U3") (pin "P$29") (pinfunction "TXRX3M_C_P$29") (pintype "bidirectional"))
    )
    (net (code "142") (name "TXRX3M_D") (class "Default")
      (node (ref "J4") (pin "P3_9") (pinfunction "P3_TRD4-_P3_9") (pintype "bidirectional"))
      (node (ref "U3") (pin "P$32") (pinfunction "TXRX3M_D_P$32") (pintype "bidirectional"))
    )
    (net (code "143") (name "TXRX3P_A") (class "Default")
      (node (ref "J4") (pin "P3_2") (pinfunction "P3_TRD1+_P3_2") (pintype "bidirectional"))
      (node (ref "U3") (pin "P$24") (pinfunction "TXRX3P_A_P$24") (pintype "bidirectional"))
    )
    (net (code "144") (name "TXRX3P_B") (class "Default")
      (node (ref "J4") (pin "P3_4") (pinfunction "P3_TRD2+_P3_4") (pintype "bidirectional"))
      (node (ref "U3") (pin "P$26") (pinfunction "TXRX3P_B_P$26") (pintype "bidirectional"))
    )
    (net (code "145") (name "TXRX3P_C") (class "Default")
      (node (ref "J4") (pin "P3_6") (pinfunction "P3_TRD3+_P3_6") (pintype "bidirectional"))
      (node (ref "U3") (pin "P$28") (pinfunction "TXRX3P_C_P$28") (pintype "bidirectional"))
    )
    (net (code "146") (name "TXRX3P_D") (class "Default")
      (node (ref "J4") (pin "P3_8") (pinfunction "P3_TRD4+_P3_8") (pintype "bidirectional"))
      (node (ref "U3") (pin "P$31") (pinfunction "TXRX3P_D_P$31") (pintype "bidirectional"))
    )
    (net (code "147") (name "TXRX4M_A") (class "Default")
      (node (ref "J4") (pin "P4_3") (pinfunction "P4_TRD1-_P4_3") (pintype "bidirectional"))
      (node (ref "U3") (pin "P$35") (pinfunction "TXRX4M_A_P$35") (pintype "bidirectional"))
    )
    (net (code "148") (name "TXRX4M_B") (class "Default")
      (node (ref "J4") (pin "P4_5") (pinfunction "P4_TRD2-_P4_5") (pintype "bidirectional"))
      (node (ref "U3") (pin "P$38") (pinfunction "TXRX4M_B_P$38") (pintype "bidirectional"))
    )
    (net (code "149") (name "TXRX4M_C") (class "Default")
      (node (ref "J4") (pin "P4_7") (pinfunction "P4_TRD3-_P4_7") (pintype "bidirectional"))
      (node (ref "U3") (pin "P$40") (pinfunction "TXRX4M_C_P$40") (pintype "bidirectional"))
    )
    (net (code "150") (name "TXRX4M_D") (class "Default")
      (node (ref "J4") (pin "P4_9") (pinfunction "P4_TRD4-_P4_9") (pintype "bidirectional"))
      (node (ref "U3") (pin "P$43") (pinfunction "TXRX4M_D_P$43") (pintype "bidirectional"))
    )
    (net (code "151") (name "TXRX4P_A") (class "Default")
      (node (ref "J4") (pin "P4_2") (pinfunction "P4_TRD1+_P4_2") (pintype "bidirectional"))
      (node (ref "U3") (pin "P$34") (pinfunction "TXRX4P_A_P$34") (pintype "bidirectional"))
    )
    (net (code "152") (name "TXRX4P_B") (class "Default")
      (node (ref "J4") (pin "P4_4") (pinfunction "P4_TRD2+_P4_4") (pintype "bidirectional"))
      (node (ref "U3") (pin "P$37") (pinfunction "TXRX4P_B_P$37") (pintype "bidirectional"))
    )
    (net (code "153") (name "TXRX4P_C") (class "Default")
      (node (ref "J4") (pin "P4_6") (pinfunction "P4_TRD3+_P4_6") (pintype "bidirectional"))
      (node (ref "U3") (pin "P$39") (pinfunction "TXRX4P_C_P$39") (pintype "bidirectional"))
    )
    (net (code "154") (name "TXRX4P_D") (class "Default")
      (node (ref "J4") (pin "P4_8") (pinfunction "P4_TRD4+_P4_8") (pintype "bidirectional"))
      (node (ref "U3") (pin "P$42") (pinfunction "TXRX4P_D_P$42") (pintype "bidirectional"))
    )
    (net (code "155") (name "TXRX5M_A") (class "Default")
      (node (ref "T1") (pin "P$22") (pinfunction "MX1-_P$22") (pintype "bidirectional"))
      (node (ref "U3") (pin "P$113") (pinfunction "TXRX5M_A_P$113") (pintype "bidirectional"))
    )
    (net (code "156") (name "TXRX5M_B") (class "Default")
      (node (ref "T1") (pin "P$19") (pinfunction "MX2-_P$19") (pintype "bidirectional"))
      (node (ref "U3") (pin "P$116") (pinfunction "TXRX5M_B_P$116") (pintype "bidirectional"))
    )
    (net (code "157") (name "TXRX5M_C") (class "Default")
      (node (ref "T1") (pin "P$16") (pinfunction "MX3-_P$16") (pintype "bidirectional"))
      (node (ref "U3") (pin "P$118") (pinfunction "TXRX5M_C_P$118") (pintype "bidirectional"))
    )
    (net (code "158") (name "TXRX5M_D") (class "Default")
      (node (ref "T1") (pin "P$13") (pinfunction "MX4-_P$13") (pintype "bidirectional"))
      (node (ref "U3") (pin "P$121") (pinfunction "TXRX5M_D_P$121") (pintype "bidirectional"))
    )
    (net (code "159") (name "TXRX5P_A") (class "Default")
      (node (ref "T1") (pin "P$23") (pinfunction "MX1+_P$23") (pintype "bidirectional"))
      (node (ref "U3") (pin "P$112") (pinfunction "TXRX5P_A_P$112") (pintype "bidirectional"))
    )
    (net (code "160") (name "TXRX5P_B") (class "Default")
      (node (ref "T1") (pin "P$20") (pinfunction "MX2+_P$20") (pintype "bidirectional"))
      (node (ref "U3") (pin "P$115") (pinfunction "TXRX5P_B_P$115") (pintype "bidirectional"))
    )
    (net (code "161") (name "TXRX5P_C") (class "Default")
      (node (ref "T1") (pin "P$17") (pinfunction "MX3+_P$17") (pintype "bidirectional"))
      (node (ref "U3") (pin "P$117") (pinfunction "TXRX5P_C_P$117") (pintype "bidirectional"))
    )
    (net (code "162") (name "TXRX5P_D") (class "Default")
      (node (ref "T1") (pin "P$14") (pinfunction "MX4+_P$14") (pintype "bidirectional"))
      (node (ref "U3") (pin "P$120") (pinfunction "TXRX5P_D_P$120") (pintype "bidirectional"))
    )
    (net (code "163") (name "UART_RXD") (class "Default")
      (node (ref "U$1") (pin "P$51") (pinfunction "GPIO15_P$51") (pintype "bidirectional"))
      (node (ref "U4") (pin "20") (pinfunction "TXD_20") (pintype "output"))
    )
    (net (code "164") (name "UART_TXD") (class "Default")
      (node (ref "U$1") (pin "P$55") (pinfunction "GPIO14_P$55") (pintype "bidirectional"))
      (node (ref "U4") (pin "4") (pinfunction "RXD_4") (pintype "input"))
    )
    (net (code "165") (name "VBUS") (class "Default")
      (node (ref "C36") (pin "1") (pinfunction "1_1") (pintype "passive"))
      (node (ref "U$2") (pin "1") (pinfunction "VBUS_1") (pintype "bidirectional"))
      (node (ref "U4") (pin "15") (pinfunction "VCC_15") (pintype "power_in"))
    )
    (net (code "166") (name "VDDHS_2V5") (class "Default")
      (node (ref "C72") (pin "1") (pinfunction "1_1") (pintype "passive"))
      (node (ref "C73") (pin "1") (pinfunction "1_1") (pintype "passive"))
      (node (ref "C74") (pin "1") (pinfunction "1_1") (pintype "passive"))
      (node (ref "FB4") (pin "2") (pinfunction "2_2") (pintype "passive"))
      (node (ref "U3") (pin "P$72") (pinfunction "VDDHS_P$72") (pintype "bidirectional"))
      (node (ref "U3") (pin "P$83") (pinfunction "VDDHS_P$83") (pintype "bidirectional"))
    )
    (net (code "167") (name "VDDLS_1V2") (class "Default")
      (node (ref "C37") (pin "1") (pinfunction "1_1") (pintype "passive"))
      (node (ref "C50") (pin "1") (pinfunction "1_1") (pintype "passive"))
      (node (ref "C51") (pin "1") (pinfunction "1_1") (pintype "passive"))
      (node (ref "FB1") (pin "2") (pinfunction "2_2") (pintype "passive"))
      (node (ref "U3") (pin "P$71") (pinfunction "VDDLS_P$71") (pintype "bidirectional"))
      (node (ref "U3") (pin "P$84") (pinfunction "VDDLS_P$84") (pintype "bidirectional"))
    )
    (net (code "168") (name "VIN") (class "Default")
      (node (ref "C10") (pin "1") (pinfunction "1_1") (pintype "passive"))
      (node (ref "C20") (pin "1") (pinfunction "1_1") (pintype "passive"))
      (node (ref "C21") (pin "1") (pinfunction "1_1") (pintype "passive"))
      (node (ref "C22") (pin "1") (pinfunction "1_1") (pintype "passive"))
      (node (ref "C23") (pin "1") (pinfunction "1_1") (pintype "passive"))
      (node (ref "C24") (pin "1") (pinfunction "1_1") (pintype "passive"))
      (node (ref "C25") (pin "1") (pinfunction "1_1") (pintype "passive"))
      (node (ref "C33") (pin "1") (pinfunction "1_1") (pintype "passive"))
      (node (ref "C34") (pin "1") (pinfunction "1_1") (pintype "passive"))
      (node (ref "C5") (pin "1") (pinfunction "1_1") (pintype "passive"))
      (node (ref "C6") (pin "1") (pinfunction "1_1") (pintype "passive"))
      (node (ref "C7") (pin "1") (pinfunction "1_1") (pintype "passive"))
      (node (ref "C8") (pin "1") (pinfunction "1_1") (pintype "passive"))
      (node (ref "C9") (pin "1") (pinfunction "1_1") (pintype "passive"))
      (node (ref "Q1") (pin "1") (pinfunction "S_1") (pintype "bidirectional"))
      (node (ref "Q1") (pin "2") (pinfunction "S_2") (pintype "bidirectional"))
      (node (ref "Q1") (pin "3") (pinfunction "S_3") (pintype "bidirectional"))
      (node (ref "U1") (pin "P$2") (pinfunction "VIN_P$2") (pintype "bidirectional"))
      (node (ref "U1") (pin "P$3") (pinfunction "EN_P$3") (pintype "bidirectional"))
      (node (ref "U2") (pin "P$2") (pinfunction "VIN_P$2") (pintype "bidirectional"))
      (node (ref "U2") (pin "P$3") (pinfunction "EN_P$3") (pintype "bidirectional"))
      (node (ref "Z1") (pin "3") (pinfunction "C_3") (pintype "passive"))
    )
    (net (code "169") (name "unconnected-(J1-PadCD)") (class "Default")
      (node (ref "J1") (pin "CD") (pinfunction "CD_CD") (pintype "bidirectional"))
    )
    (net (code "170") (name "unconnected-(J3-MOD_ABS-Pad6)") (class "Default")
      (node (ref "J3") (pin "6") (pinfunction "MOD_ABS_6") (pintype "bidirectional"))
    )
    (net (code "171") (name "unconnected-(U$1-AIN_P0-PadP$96)") (class "Default")
      (node (ref "U$1") (pin "P$96") (pinfunction "AIN_P0_P$96") (pintype "bidirectional"))
    )
    (net (code "172") (name "unconnected-(U$1-AIN_P1-PadP$94)") (class "Default")
      (node (ref "U$1") (pin "P$94") (pinfunction "AIN_P1_P$94") (pintype "bidirectional"))
    )
    (net (code "173") (name "unconnected-(U$1-CAM0_C_N-PadP$140)") (class "Default")
      (node (ref "U$1") (pin "P$140") (pinfunction "CAM0_C_N_P$140") (pintype "bidirectional"))
    )
    (net (code "174") (name "unconnected-(U$1-CAM0_C_P-PadP$142)") (class "Default")
      (node (ref "U$1") (pin "P$142") (pinfunction "CAM0_C_P_P$142") (pintype "bidirectional"))
    )
    (net (code "175") (name "unconnected-(U$1-CAM0_D0_N-PadP$128)") (class "Default")
      (node (ref "U$1") (pin "P$128") (pinfunction "CAM0_D0_N_P$128") (pintype "bidirectional"))
    )
    (net (code "176") (name "unconnected-(U$1-CAM0_D0_P-PadP$130)") (class "Default")
      (node (ref "U$1") (pin "P$130") (pinfunction "CAM0_D0_P_P$130") (pintype "bidirectional"))
    )
    (net (code "177") (name "unconnected-(U$1-CAM0_D1_N-PadP$134)") (class "Default")
      (node (ref "U$1") (pin "P$134") (pinfunction "CAM0_D1_N_P$134") (pintype "bidirectional"))
    )
    (net (code "178") (name "unconnected-(U$1-CAM0_D1_P-PadP$136)") (class "Default")
      (node (ref "U$1") (pin "P$136") (pinfunction "CAM0_D1_P_P$136") (pintype "bidirectional"))
    )
    (net (code "179") (name "unconnected-(U$1-CAM1_C_N-PadP$127)") (class "Default")
      (node (ref "U$1") (pin "P$127") (pinfunction "CAM1_C_N_P$127") (pintype "bidirectional"))
    )
    (net (code "180") (name "unconnected-(U$1-CAM1_C_P-PadP$129)") (class "Default")
      (node (ref "U$1") (pin "P$129") (pinfunction "CAM1_C_P_P$129") (pintype "bidirectional"))
    )
    (net (code "181") (name "unconnected-(U$1-CAM1_D0_N-PadP$115)") (class "Default")
      (node (ref "U$1") (pin "P$115") (pinfunction "CAM1_D0_N_P$115") (pintype "bidirectional"))
    )
    (net (code "182") (name "unconnected-(U$1-CAM1_D0_P-PadP$117)") (class "Default")
      (node (ref "U$1") (pin "P$117") (pinfunction "CAM1_D0_P_P$117") (pintype "bidirectional"))
    )
    (net (code "183") (name "unconnected-(U$1-CAM1_D1_N-PadP$121)") (class "Default")
      (node (ref "U$1") (pin "P$121") (pinfunction "CAM1_D1_N_P$121") (pintype "bidirectional"))
    )
    (net (code "184") (name "unconnected-(U$1-CAM1_D1_P-PadP$123)") (class "Default")
      (node (ref "U$1") (pin "P$123") (pinfunction "CAM1_D1_P_P$123") (pintype "bidirectional"))
    )
    (net (code "185") (name "unconnected-(U$1-CAM1_D2_N-PadP$133)") (class "Default")
      (node (ref "U$1") (pin "P$133") (pinfunction "CAM1_D2_N_P$133") (pintype "bidirectional"))
    )
    (net (code "186") (name "unconnected-(U$1-CAM1_D2_P-PadP$135)") (class "Default")
      (node (ref "U$1") (pin "P$135") (pinfunction "CAM1_D2_P_P$135") (pintype "bidirectional"))
    )
    (net (code "187") (name "unconnected-(U$1-CAM1_D3_N-PadP$139)") (class "Default")
      (node (ref "U$1") (pin "P$139") (pinfunction "CAM1_D3_N_P$139") (pintype "bidirectional"))
    )
    (net (code "188") (name "unconnected-(U$1-CAM1_D3_P-PadP$141)") (class "Default")
      (node (ref "U$1") (pin "P$141") (pinfunction "CAM1_D3_P_P$141") (pintype "bidirectional"))
    )
    (net (code "189") (name "unconnected-(U$1-CAM_GPIO-PadP$97)") (class "Default")
      (node (ref "U$1") (pin "P$97") (pinfunction "CAM_GPIO_P$97") (pintype "bidirectional"))
    )
    (net (code "190") (name "unconnected-(U$1-DSI0_C_N-PadP$169)") (class "Default")
      (node (ref "U$1") (pin "P$169") (pinfunction "DSI0_C_N_P$169") (pintype "bidirectional"))
    )
    (net (code "191") (name "unconnected-(U$1-DSI0_C_P-PadP$171)") (class "Default")
      (node (ref "U$1") (pin "P$171") (pinfunction "DSI0_C_P_P$171") (pintype "bidirectional"))
    )
    (net (code "192") (name "unconnected-(U$1-DSI0_D0_N-PadP$157)") (class "Default")
      (node (ref "U$1") (pin "P$157") (pinfunction "DSI0_D0_N_P$157") (pintype "bidirectional"))
    )
    (net (code "193") (name "unconnected-(U$1-DSI0_D0_P-PadP$159)") (class "Default")
      (node (ref "U$1") (pin "P$159") (pinfunction "DSI0_D0_P_P$159") (pintype "bidirectional"))
    )
    (net (code "194") (name "unconnected-(U$1-DSI0_D1_N-PadP$163)") (class "Default")
      (node (ref "U$1") (pin "P$163") (pinfunction "DSI0_D1_N_P$163") (pintype "bidirectional"))
    )
    (net (code "195") (name "unconnected-(U$1-DSI0_D1_P-PadP$165)") (class "Default")
      (node (ref "U$1") (pin "P$165") (pinfunction "DSI0_D1_P_P$165") (pintype "bidirectional"))
    )
    (net (code "196") (name "unconnected-(U$1-DSI1_C_N-PadP$187)") (class "Default")
      (node (ref "U$1") (pin "P$187") (pinfunction "DSI1_C_N_P$187") (pintype "bidirectional"))
    )
    (net (code "197") (name "unconnected-(U$1-DSI1_C_P-PadP$189)") (class "Default")
      (node (ref "U$1") (pin "P$189") (pinfunction "DSI1_C_P_P$189") (pintype "bidirectional"))
    )
    (net (code "198") (name "unconnected-(U$1-DSI1_D0_N-PadP$175)") (class "Default")
      (node (ref "U$1") (pin "P$175") (pinfunction "DSI1_D0_N_P$175") (pintype "bidirectional"))
    )
    (net (code "199") (name "unconnected-(U$1-DSI1_D0_P-PadP$177)") (class "Default")
      (node (ref "U$1") (pin "P$177") (pinfunction "DSI1_D0_P_P$177") (pintype "bidirectional"))
    )
    (net (code "200") (name "unconnected-(U$1-DSI1_D1_N-PadP$181)") (class "Default")
      (node (ref "U$1") (pin "P$181") (pinfunction "DSI1_D1_N_P$181") (pintype "bidirectional"))
    )
    (net (code "201") (name "unconnected-(U$1-DSI1_D1_P-PadP$183)") (class "Default")
      (node (ref "U$1") (pin "P$183") (pinfunction "DSI1_D1_P_P$183") (pintype "bidirectional"))
    )
    (net (code "202") (name "unconnected-(U$1-DSI1_D2_N-PadP$193)") (class "Default")
      (node (ref "U$1") (pin "P$193") (pinfunction "DSI1_D2_N_P$193") (pintype "bidirectional"))
    )
    (net (code "203") (name "unconnected-(U$1-DSI1_D2_P-PadP$195)") (class "Default")
      (node (ref "U$1") (pin "P$195") (pinfunction "DSI1_D2_P_P$195") (pintype "bidirectional"))
    )
    (net (code "204") (name "unconnected-(U$1-DSI1_D3_N-PadP$194)") (class "Default")
      (node (ref "U$1") (pin "P$194") (pinfunction "DSI1_D3_N_P$194") (pintype "bidirectional"))
    )
    (net (code "205") (name "unconnected-(U$1-DSI1_D3_P-PadP$196)") (class "Default")
      (node (ref "U$1") (pin "P$196") (pinfunction "DSI1_D3_P_P$196") (pintype "bidirectional"))
    )
    (net (code "206") (name "unconnected-(U$1-EEPROM_NWP-PadP$20)") (class "Default")
      (node (ref "U$1") (pin "P$20") (pinfunction "EEPROM_NWP_P$20") (pintype "bidirectional"))
    )
    (net (code "207") (name "unconnected-(U$1-ETH_NLED1-PadP$19)") (class "Default")
      (node (ref "U$1") (pin "P$19") (pinfunction "ETH_NLED1_P$19") (pintype "bidirectional"))
    )
    (net (code "208") (name "unconnected-(U$1-ETH_SYNC_IN-PadP$16)") (class "Default")
      (node (ref "U$1") (pin "P$16") (pinfunction "ETH_SYNC_IN_P$16") (pintype "bidirectional"))
    )
    (net (code "209") (name "unconnected-(U$1-ETH_SYNC_OUT-PadP$18)") (class "Default")
      (node (ref "U$1") (pin "P$18") (pinfunction "ETH_SYNC_OUT_P$18") (pintype "bidirectional"))
    )
    (net (code "210") (name "unconnected-(U$1-GND-PadP$107)") (class "Default")
      (node (ref "U$1") (pin "P$107") (pinfunction "GND_P$107") (pintype "bidirectional"))
    )
    (net (code "211") (name "unconnected-(U$1-GND-PadP$108)") (class "Default")
      (node (ref "U$1") (pin "P$108") (pinfunction "GND_P$108") (pintype "bidirectional"))
    )
    (net (code "212") (name "unconnected-(U$1-GND-PadP$113)") (class "Default")
      (node (ref "U$1") (pin "P$113") (pinfunction "GND_P$113") (pintype "bidirectional"))
    )
    (net (code "213") (name "unconnected-(U$1-GND-PadP$114)") (class "Default")
      (node (ref "U$1") (pin "P$114") (pinfunction "GND_P$114") (pintype "bidirectional"))
    )
    (net (code "214") (name "unconnected-(U$1-GND-PadP$119)") (class "Default")
      (node (ref "U$1") (pin "P$119") (pinfunction "GND_P$119") (pintype "bidirectional"))
    )
    (net (code "215") (name "unconnected-(U$1-GND-PadP$120)") (class "Default")
      (node (ref "U$1") (pin "P$120") (pinfunction "GND_P$120") (pintype "bidirectional"))
    )
    (net (code "216") (name "unconnected-(U$1-GND-PadP$125)") (class "Default")
      (node (ref "U$1") (pin "P$125") (pinfunction "GND_P$125") (pintype "bidirectional"))
    )
    (net (code "217") (name "unconnected-(U$1-GND-PadP$126)") (class "Default")
      (node (ref "U$1") (pin "P$126") (pinfunction "GND_P$126") (pintype "bidirectional"))
    )
    (net (code "218") (name "unconnected-(U$1-GND-PadP$131)") (class "Default")
      (node (ref "U$1") (pin "P$131") (pinfunction "GND_P$131") (pintype "bidirectional"))
    )
    (net (code "219") (name "unconnected-(U$1-GND-PadP$132)") (class "Default")
      (node (ref "U$1") (pin "P$132") (pinfunction "GND_P$132") (pintype "bidirectional"))
    )
    (net (code "220") (name "unconnected-(U$1-GND-PadP$137)") (class "Default")
      (node (ref "U$1") (pin "P$137") (pinfunction "GND_P$137") (pintype "bidirectional"))
    )
    (net (code "221") (name "unconnected-(U$1-GND-PadP$138)") (class "Default")
      (node (ref "U$1") (pin "P$138") (pinfunction "GND_P$138") (pintype "bidirectional"))
    )
    (net (code "222") (name "unconnected-(U$1-GND-PadP$144)") (class "Default")
      (node (ref "U$1") (pin "P$144") (pinfunction "GND_P$144") (pintype "bidirectional"))
    )
    (net (code "223") (name "unconnected-(U$1-GND-PadP$150)") (class "Default")
      (node (ref "U$1") (pin "P$150") (pinfunction "GND_P$150") (pintype "bidirectional"))
    )
    (net (code "224") (name "unconnected-(U$1-GND-PadP$155)") (class "Default")
      (node (ref "U$1") (pin "P$155") (pinfunction "GND_P$155") (pintype "bidirectional"))
    )
    (net (code "225") (name "unconnected-(U$1-GND-PadP$156)") (class "Default")
      (node (ref "U$1") (pin "P$156") (pinfunction "GND_P$156") (pintype "bidirectional"))
    )
    (net (code "226") (name "unconnected-(U$1-GND-PadP$161)") (class "Default")
      (node (ref "U$1") (pin "P$161") (pinfunction "GND_P$161") (pintype "bidirectional"))
    )
    (net (code "227") (name "unconnected-(U$1-GND-PadP$162)") (class "Default")
      (node (ref "U$1") (pin "P$162") (pinfunction "GND_P$162") (pintype "bidirectional"))
    )
    (net (code "228") (name "unconnected-(U$1-GND-PadP$167)") (class "Default")
      (node (ref "U$1") (pin "P$167") (pinfunction "GND_P$167") (pintype "bidirectional"))
    )
    (net (code "229") (name "unconnected-(U$1-GND-PadP$168)") (class "Default")
      (node (ref "U$1") (pin "P$168") (pinfunction "GND_P$168") (pintype "bidirectional"))
    )
    (net (code "230") (name "unconnected-(U$1-GND-PadP$173)") (class "Default")
      (node (ref "U$1") (pin "P$173") (pinfunction "GND_P$173") (pintype "bidirectional"))
    )
    (net (code "231") (name "unconnected-(U$1-GND-PadP$174)") (class "Default")
      (node (ref "U$1") (pin "P$174") (pinfunction "GND_P$174") (pintype "bidirectional"))
    )
    (net (code "232") (name "unconnected-(U$1-GND-PadP$179)") (class "Default")
      (node (ref "U$1") (pin "P$179") (pinfunction "GND_P$179") (pintype "bidirectional"))
    )
    (net (code "233") (name "unconnected-(U$1-GND-PadP$180)") (class "Default")
      (node (ref "U$1") (pin "P$180") (pinfunction "GND_P$180") (pintype "bidirectional"))
    )
    (net (code "234") (name "unconnected-(U$1-GND-PadP$185)") (class "Default")
      (node (ref "U$1") (pin "P$185") (pinfunction "GND_P$185") (pintype "bidirectional"))
    )
    (net (code "235") (name "unconnected-(U$1-GND-PadP$186)") (class "Default")
      (node (ref "U$1") (pin "P$186") (pinfunction "GND_P$186") (pintype "bidirectional"))
    )
    (net (code "236") (name "unconnected-(U$1-GND-PadP$191)") (class "Default")
      (node (ref "U$1") (pin "P$191") (pinfunction "GND_P$191") (pintype "bidirectional"))
    )
    (net (code "237") (name "unconnected-(U$1-GND-PadP$192)") (class "Default")
      (node (ref "U$1") (pin "P$192") (pinfunction "GND_P$192") (pintype "bidirectional"))
    )
    (net (code "238") (name "unconnected-(U$1-GND-PadP$197)") (class "Default")
      (node (ref "U$1") (pin "P$197") (pinfunction "GND_P$197") (pintype "bidirectional"))
    )
    (net (code "239") (name "unconnected-(U$1-GND-PadP$198)") (class "Default")
      (node (ref "U$1") (pin "P$198") (pinfunction "GND_P$198") (pintype "bidirectional"))
    )
    (net (code "240") (name "unconnected-(U$1-GPIO2-PadP$58)") (class "Default")
      (node (ref "U$1") (pin "P$58") (pinfunction "GPIO2_P$58") (pintype "bidirectional"))
    )
    (net (code "241") (name "unconnected-(U$1-GPIO3-PadP$56)") (class "Default")
      (node (ref "U$1") (pin "P$56") (pinfunction "GPIO3_P$56") (pintype "bidirectional"))
    )
    (net (code "242") (name "unconnected-(U$1-GPIO4-PadP$54)") (class "Default")
      (node (ref "U$1") (pin "P$54") (pinfunction "GPIO4_P$54") (pintype "bidirectional"))
    )
    (net (code "243") (name "unconnected-(U$1-GPIO5-PadP$34)") (class "Default")
      (node (ref "U$1") (pin "P$34") (pinfunction "GPIO5_P$34") (pintype "bidirectional"))
    )
    (net (code "244") (name "unconnected-(U$1-GPIO6-PadP$30)") (class "Default")
      (node (ref "U$1") (pin "P$30") (pinfunction "GPIO6_P$30") (pintype "bidirectional"))
    )
    (net (code "245") (name "unconnected-(U$1-GPIO12-PadP$31)") (class "Default")
      (node (ref "U$1") (pin "P$31") (pinfunction "GPIO12_P$31") (pintype "bidirectional"))
    )
    (net (code "246") (name "unconnected-(U$1-GPIO13-PadP$28)") (class "Default")
      (node (ref "U$1") (pin "P$28") (pinfunction "GPIO13_P$28") (pintype "bidirectional"))
    )
    (net (code "247") (name "unconnected-(U$1-GPIO16-PadP$29)") (class "Default")
      (node (ref "U$1") (pin "P$29") (pinfunction "GPIO16_P$29") (pintype "bidirectional"))
    )
    (net (code "248") (name "unconnected-(U$1-GPIO17-PadP$50)") (class "Default")
      (node (ref "U$1") (pin "P$50") (pinfunction "GPIO17_P$50") (pintype "bidirectional"))
    )
    (net (code "249") (name "unconnected-(U$1-GPIO18-PadP$49)") (class "Default")
      (node (ref "U$1") (pin "P$49") (pinfunction "GPIO18_P$49") (pintype "bidirectional"))
    )
    (net (code "250") (name "unconnected-(U$1-GPIO19-PadP$26)") (class "Default")
      (node (ref "U$1") (pin "P$26") (pinfunction "GPIO19_P$26") (pintype "bidirectional"))
    )
    (net (code "251") (name "unconnected-(U$1-GPIO20-PadP$27)") (class "Default")
      (node (ref "U$1") (pin "P$27") (pinfunction "GPIO20_P$27") (pintype "bidirectional"))
    )
    (net (code "252") (name "unconnected-(U$1-GPIO22-PadP$46)") (class "Default")
      (node (ref "U$1") (pin "P$46") (pinfunction "GPIO22_P$46") (pintype "bidirectional"))
    )
    (net (code "253") (name "unconnected-(U$1-GPIO23-PadP$47)") (class "Default")
      (node (ref "U$1") (pin "P$47") (pinfunction "GPIO23_P$47") (pintype "bidirectional"))
    )
    (net (code "254") (name "unconnected-(U$1-GPIO24-PadP$45)") (class "Default")
      (node (ref "U$1") (pin "P$45") (pinfunction "GPIO24_P$45") (pintype "bidirectional"))
    )
    (net (code "255") (name "unconnected-(U$1-GPIO25-PadP$41)") (class "Default")
      (node (ref "U$1") (pin "P$41") (pinfunction "GPIO25_P$41") (pintype "bidirectional"))
    )
    (net (code "256") (name "unconnected-(U$1-GPIO26-PadP$24)") (class "Default")
      (node (ref "U$1") (pin "P$24") (pinfunction "GPIO26_P$24") (pintype "bidirectional"))
    )
    (net (code "257") (name "unconnected-(U$1-GPIO27-PadP$48)") (class "Default")
      (node (ref "U$1") (pin "P$48") (pinfunction "GPIO27_P$48") (pintype "bidirectional"))
    )
    (net (code "258") (name "unconnected-(U$1-HDMI0_CEC-PadP$151)") (class "Default")
      (node (ref "U$1") (pin "P$151") (pinfunction "HDMI0_CEC_P$151") (pintype "bidirectional"))
    )
    (net (code "259") (name "unconnected-(U$1-HDMI0_CLK_N-PadP$190)") (class "Default")
      (node (ref "U$1") (pin "P$190") (pinfunction "HDMI0_CLK_N_P$190") (pintype "bidirectional"))
    )
    (net (code "260") (name "unconnected-(U$1-HDMI0_CLK_P-PadP$188)") (class "Default")
      (node (ref "U$1") (pin "P$188") (pinfunction "HDMI0_CLK_P_P$188") (pintype "bidirectional"))
    )
    (net (code "261") (name "unconnected-(U$1-HDMI0_HOTPLG-PadP$153)") (class "Default")
      (node (ref "U$1") (pin "P$153") (pinfunction "HDMI0_HOTPLG_P$153") (pintype "bidirectional"))
    )
    (net (code "262") (name "unconnected-(U$1-HDMI0_SCL-PadP$200)") (class "Default")
      (node (ref "U$1") (pin "P$200") (pinfunction "HDMI0_SCL_P$200") (pintype "bidirectional"))
    )
    (net (code "263") (name "unconnected-(U$1-HDMI0_SDA-PadP$199)") (class "Default")
      (node (ref "U$1") (pin "P$199") (pinfunction "HDMI0_SDA_P$199") (pintype "bidirectional"))
    )
    (net (code "264") (name "unconnected-(U$1-HDMI0_TX0_N-PadP$184)") (class "Default")
      (node (ref "U$1") (pin "P$184") (pinfunction "HDMI0_TX0_N_P$184") (pintype "bidirectional"))
    )
    (net (code "265") (name "unconnected-(U$1-HDMI0_TX0_P-PadP$182)") (class "Default")
      (node (ref "U$1") (pin "P$182") (pinfunction "HDMI0_TX0_P_P$182") (pintype "bidirectional"))
    )
    (net (code "266") (name "unconnected-(U$1-HDMI0_TX1_N-PadP$178)") (class "Default")
      (node (ref "U$1") (pin "P$178") (pinfunction "HDMI0_TX1_N_P$178") (pintype "bidirectional"))
    )
    (net (code "267") (name "unconnected-(U$1-HDMI0_TX1_P-PadP$176)") (class "Default")
      (node (ref "U$1") (pin "P$176") (pinfunction "HDMI0_TX1_P_P$176") (pintype "bidirectional"))
    )
    (net (code "268") (name "unconnected-(U$1-HDMI0_TX2_N-PadP$172)") (class "Default")
      (node (ref "U$1") (pin "P$172") (pinfunction "HDMI0_TX2_N_P$172") (pintype "bidirectional"))
    )
    (net (code "269") (name "unconnected-(U$1-HDMI0_TX2_P-PadP$170)") (class "Default")
      (node (ref "U$1") (pin "P$170") (pinfunction "HDMI0_TX2_P_P$170") (pintype "bidirectional"))
    )
    (net (code "270") (name "unconnected-(U$1-HDMI1_CEC-PadP$149)") (class "Default")
      (node (ref "U$1") (pin "P$149") (pinfunction "HDMI1_CEC_P$149") (pintype "bidirectional"))
    )
    (net (code "271") (name "unconnected-(U$1-HDMI1_CLK_N-PadP$166)") (class "Default")
      (node (ref "U$1") (pin "P$166") (pinfunction "HDMI1_CLK_N_P$166") (pintype "bidirectional"))
    )
    (net (code "272") (name "unconnected-(U$1-HDMI1_CLK_P-PadP$164)") (class "Default")
      (node (ref "U$1") (pin "P$164") (pinfunction "HDMI1_CLK_P_P$164") (pintype "bidirectional"))
    )
    (net (code "273") (name "unconnected-(U$1-HDMI1_HOTPLG-PadP$143)") (class "Default")
      (node (ref "U$1") (pin "P$143") (pinfunction "HDMI1_HOTPLG_P$143") (pintype "bidirectional"))
    )
    (net (code "274") (name "unconnected-(U$1-HDMI1_SCL-PadP$147)") (class "Default")
      (node (ref "U$1") (pin "P$147") (pinfunction "HDMI1_SCL_P$147") (pintype "bidirectional"))
    )
    (net (code "275") (name "unconnected-(U$1-HDMI1_SDA-PadP$145)") (class "Default")
      (node (ref "U$1") (pin "P$145") (pinfunction "HDMI1_SDA_P$145") (pintype "bidirectional"))
    )
    (net (code "276") (name "unconnected-(U$1-HDMI1_TX0_N-PadP$160)") (class "Default")
      (node (ref "U$1") (pin "P$160") (pinfunction "HDMI1_TX0_N_P$160") (pintype "bidirectional"))
    )
    (net (code "277") (name "unconnected-(U$1-HDMI1_TX0_P-PadP$158)") (class "Default")
      (node (ref "U$1") (pin "P$158") (pinfunction "HDMI1_TX0_P_P$158") (pintype "bidirectional"))
    )
    (net (code "278") (name "unconnected-(U$1-HDMI1_TX1_N-PadP$154)") (class "Default")
      (node (ref "U$1") (pin "P$154") (pinfunction "HDMI1_TX1_N_P$154") (pintype "bidirectional"))
    )
    (net (code "279") (name "unconnected-(U$1-HDMI1_TX1_P-PadP$152)") (class "Default")
      (node (ref "U$1") (pin "P$152") (pinfunction "HDMI1_TX1_P_P$152") (pintype "bidirectional"))
    )
    (net (code "280") (name "unconnected-(U$1-HDMI1_TX2_N-PadP$148)") (class "Default")
      (node (ref "U$1") (pin "P$148") (pinfunction "HDMI1_TX2_N_P$148") (pintype "bidirectional"))
    )
    (net (code "281") (name "unconnected-(U$1-HDMI1_TX2_P-PadP$146)") (class "Default")
      (node (ref "U$1") (pin "P$146") (pinfunction "HDMI1_TX2_P_P$146") (pintype "bidirectional"))
    )
    (net (code "282") (name "unconnected-(U$1-ID_SC{slash}GPIO1-PadP$35)") (class "Default")
      (node (ref "U$1") (pin "P$35") (pinfunction "ID_SC/GPIO1_P$35") (pintype "bidirectional"))
    )
    (net (code "283") (name "unconnected-(U$1-ID_SD{slash}GPIO0-PadP$36)") (class "Default")
      (node (ref "U$1") (pin "P$36") (pinfunction "ID_SD/GPIO0_P$36") (pintype "bidirectional"))
    )
    (net (code "284") (name "unconnected-(U$1-PCIE_CLK_N-PadP$112)") (class "Default")
      (node (ref "U$1") (pin "P$112") (pinfunction "PCIE_CLK_N_P$112") (pintype "bidirectional"))
    )
    (net (code "285") (name "unconnected-(U$1-PCIE_CLK_NREQ-PadP$102)") (class "Default")
      (node (ref "U$1") (pin "P$102") (pinfunction "PCIE_CLK_NREQ_P$102") (pintype "bidirectional"))
    )
    (net (code "286") (name "unconnected-(U$1-PCIE_CLK_P-PadP$110)") (class "Default")
      (node (ref "U$1") (pin "P$110") (pinfunction "PCIE_CLK_P_P$110") (pintype "bidirectional"))
    )
    (net (code "287") (name "unconnected-(U$1-PCIE_NRST-PadP$109)") (class "Default")
      (node (ref "U$1") (pin "P$109") (pinfunction "PCIE_NRST_P$109") (pintype "bidirectional"))
    )
    (net (code "288") (name "unconnected-(U$1-PCIE_RX_N-PadP$118)") (class "Default")
      (node (ref "U$1") (pin "P$118") (pinfunction "PCIE_RX_N_P$118") (pintype "bidirectional"))
    )
    (net (code "289") (name "unconnected-(U$1-PCIE_RX_P-PadP$116)") (class "Default")
      (node (ref "U$1") (pin "P$116") (pinfunction "PCIE_RX_P_P$116") (pintype "bidirectional"))
    )
    (net (code "290") (name "unconnected-(U$1-PCIE_TX_N-PadP$124)") (class "Default")
      (node (ref "U$1") (pin "P$124") (pinfunction "PCIE_TX_N_P$124") (pintype "bidirectional"))
    )
    (net (code "291") (name "unconnected-(U$1-PCIE_TX_P-PadP$122)") (class "Default")
      (node (ref "U$1") (pin "P$122") (pinfunction "PCIE_TX_P_P$122") (pintype "bidirectional"))
    )
    (net (code "292") (name "unconnected-(U$1-PI_NLED_PWR-PadP$95)") (class "Default")
      (node (ref "U$1") (pin "P$95") (pinfunction "PI_NLED_PWR_P$95") (pintype "bidirectional"))
    )
    (net (code "293") (name "unconnected-(U$1-RUN_PG-PadP$92)") (class "Default")
      (node (ref "U$1") (pin "P$92") (pinfunction "RUN_PG_P$92") (pintype "bidirectional"))
    )
    (net (code "294") (name "unconnected-(U$1-SD_DAT4-PadP$68)") (class "Default")
      (node (ref "U$1") (pin "P$68") (pinfunction "SD_DAT4_P$68") (pintype "bidirectional"))
    )
    (net (code "295") (name "unconnected-(U$1-SD_DAT5-PadP$64)") (class "Default")
      (node (ref "U$1") (pin "P$64") (pinfunction "SD_DAT5_P$64") (pintype "bidirectional"))
    )
    (net (code "296") (name "unconnected-(U$1-SD_DAT6-PadP$72)") (class "Default")
      (node (ref "U$1") (pin "P$72") (pinfunction "SD_DAT6_P$72") (pintype "bidirectional"))
    )
    (net (code "297") (name "unconnected-(U$1-SD_DAT7-PadP$70)") (class "Default")
      (node (ref "U$1") (pin "P$70") (pinfunction "SD_DAT7_P$70") (pintype "bidirectional"))
    )
    (net (code "298") (name "unconnected-(U$1-SD_PWR_ON-PadP$75)") (class "Default")
      (node (ref "U$1") (pin "P$75") (pinfunction "SD_PWR_ON_P$75") (pintype "bidirectional"))
    )
    (net (code "299") (name "unconnected-(U$1-SD_VDD_OVRD-PadP$73)") (class "Default")
      (node (ref "U$1") (pin "P$73") (pinfunction "SD_VDD_OVRD_P$73") (pintype "bidirectional"))
    )
    (net (code "300") (name "unconnected-(U$1-USB_N-PadP$103)") (class "Default")
      (node (ref "U$1") (pin "P$103") (pinfunction "USB_N_P$103") (pintype "bidirectional"))
    )
    (net (code "301") (name "unconnected-(U$1-USB_OTG_ID-PadP$101)") (class "Default")
      (node (ref "U$1") (pin "P$101") (pinfunction "USB_OTG_ID_P$101") (pintype "bidirectional"))
    )
    (net (code "302") (name "unconnected-(U$1-USB_P-PadP$105)") (class "Default")
      (node (ref "U$1") (pin "P$105") (pinfunction "USB_P_P$105") (pintype "bidirectional"))
    )
    (net (code "303") (name "unconnected-(U$1-VDAC_COMP-PadP$111)") (class "Default")
      (node (ref "U$1") (pin "P$111") (pinfunction "VDAC_COMP_P$111") (pintype "bidirectional"))
    )
    (net (code "304") (name "unconnected-(U3-COL6-PadP$51)") (class "Default")
      (node (ref "U3") (pin "P$51") (pinfunction "COL6_P$51") (pintype "bidirectional"))
    )
    (net (code "305") (name "unconnected-(U3-CRS6-PadP$60)") (class "Default")
      (node (ref "U3") (pin "P$60") (pinfunction "CRS6_P$60") (pintype "bidirectional"))
    )
    (net (code "306") (name "unconnected-(U3-GPIO-PadP$90)") (class "Default")
      (node (ref "U3") (pin "P$90") (pinfunction "GPIO_P$90") (pintype "bidirectional"))
    )
    (net (code "307") (name "unconnected-(U3-LED5_0-PadP$102)") (class "Default")
      (node (ref "U3") (pin "P$102") (pinfunction "LED5_0_P$102") (pintype "bidirectional"))
    )
    (net (code "308") (name "unconnected-(U3-LED5_1-PadP$103)") (class "Default")
      (node (ref "U3") (pin "P$103") (pinfunction "LED5_1_P$103") (pintype "bidirectional"))
    )
    (net (code "309") (name "unconnected-(U3-PME_N-PadP$93)") (class "Default")
      (node (ref "U3") (pin "P$93") (pinfunction "PME_N_P$93") (pintype "bidirectional"))
    )
    (net (code "310") (name "unconnected-(U3-RX_CLK6{slash}REFCLKO6-PadP$57)") (class "Default")
      (node (ref "U3") (pin "P$57") (pinfunction "RX_CLK6/REFCLKO6_P$57") (pintype "bidirectional"))
    )
    (net (code "311") (name "unconnected-(U3-RX_DV6{slash}CRS_DV6{slash}RX_CTL6-PadP$58)") (class "Default")
      (node (ref "U3") (pin "P$58") (pinfunction "RX_DV6/CRS_DV6/RX_CTL6_P$58") (pintype "bidirectional"))
    )
    (net (code "312") (name "unconnected-(U3-RX_ER6-PadP$59)") (class "Default")
      (node (ref "U3") (pin "P$59") (pinfunction "RX_ER6_P$59") (pintype "bidirectional"))
    )
    (net (code "313") (name "unconnected-(U3-S_REFCLKM-PadP$74)") (class "Default")
      (node (ref "U3") (pin "P$74") (pinfunction "S_REFCLKM_P$74") (pintype "bidirectional"))
    )
    (net (code "314") (name "unconnected-(U3-S_REFCLKP-PadP$73)") (class "Default")
      (node (ref "U3") (pin "P$73") (pinfunction "S_REFCLKP_P$73") (pintype "bidirectional"))
    )
    (net (code "315") (name "unconnected-(U3-TXD6_0-PadP$55)") (class "Default")
      (node (ref "U3") (pin "P$55") (pinfunction "TXD6_0_P$55") (pintype "bidirectional"))
    )
    (net (code "316") (name "unconnected-(U3-TXD6_1-PadP$54)") (class "Default")
      (node (ref "U3") (pin "P$54") (pinfunction "TXD6_1_P$54") (pintype "bidirectional"))
    )
    (net (code "317") (name "unconnected-(U3-TXD6_2-PadP$53)") (class "Default")
      (node (ref "U3") (pin "P$53") (pinfunction "TXD6_2_P$53") (pintype "bidirectional"))
    )
    (net (code "318") (name "unconnected-(U3-TXD6_3-PadP$52)") (class "Default")
      (node (ref "U3") (pin "P$52") (pinfunction "TXD6_3_P$52") (pintype "bidirectional"))
    )
    (net (code "319") (name "unconnected-(U3-TX_CLK6{slash}REFCLKI6-PadP$48)") (class "Default")
      (node (ref "U3") (pin "P$48") (pinfunction "TX_CLK6/REFCLKI6_P$48") (pintype "bidirectional"))
    )
    (net (code "320") (name "unconnected-(U3-TX_EN6{slash}TX_CTL6-PadP$49)") (class "Default")
      (node (ref "U3") (pin "P$49") (pinfunction "TX_EN6/TX_CTL6_P$49") (pintype "bidirectional"))
    )
    (net (code "321") (name "unconnected-(U3-TX_ER6-PadP$50)") (class "Default")
      (node (ref "U3") (pin "P$50") (pinfunction "TX_ER6_P$50") (pintype "bidirectional"))
    )
    (net (code "322") (name "unconnected-(U4-CTS-Pad9)") (class "Default")
      (node (ref "U4") (pin "9") (pinfunction "CTS_9") (pintype "input"))
    )
    (net (code "323") (name "unconnected-(U4-DCD-Pad8)") (class "Default")
      (node (ref "U4") (pin "8") (pinfunction "DCD_8") (pintype "input"))
    )
    (net (code "324") (name "unconnected-(U4-DSR-Pad7)") (class "Default")
      (node (ref "U4") (pin "7") (pinfunction "DSR_7") (pintype "input"))
    )
    (net (code "325") (name "unconnected-(U4-DTR-Pad1)") (class "Default")
      (node (ref "U4") (pin "1") (pinfunction "DTR_1") (pintype "output"))
    )
    (net (code "326") (name "unconnected-(U4-RI-Pad5)") (class "Default")
      (node (ref "U4") (pin "5") (pinfunction "RI_5") (pintype "input"))
    )
    (net (code "327") (name "unconnected-(U4-RTS-Pad2)") (class "Default")
      (node (ref "U4") (pin "2") (pinfunction "RTS_2") (pintype "output"))
    )
    (net (code "328") (name "unconnected-(U4-SLEEP-Pad19)") (class "Default")
      (node (ref "U4") (pin "19") (pinfunction "SLEEP_19") (pintype "input"))
    )
    (net (code "329") (name "unconnected-(U4-TXDEN-Pad18)") (class "Default")
      (node (ref "U4") (pin "18") (pinfunction "TXDEN_18") (pintype "input"))
    )
  )
)
